# calendar-module.net
KiCad netlist of a schematic drawn in EAGLE
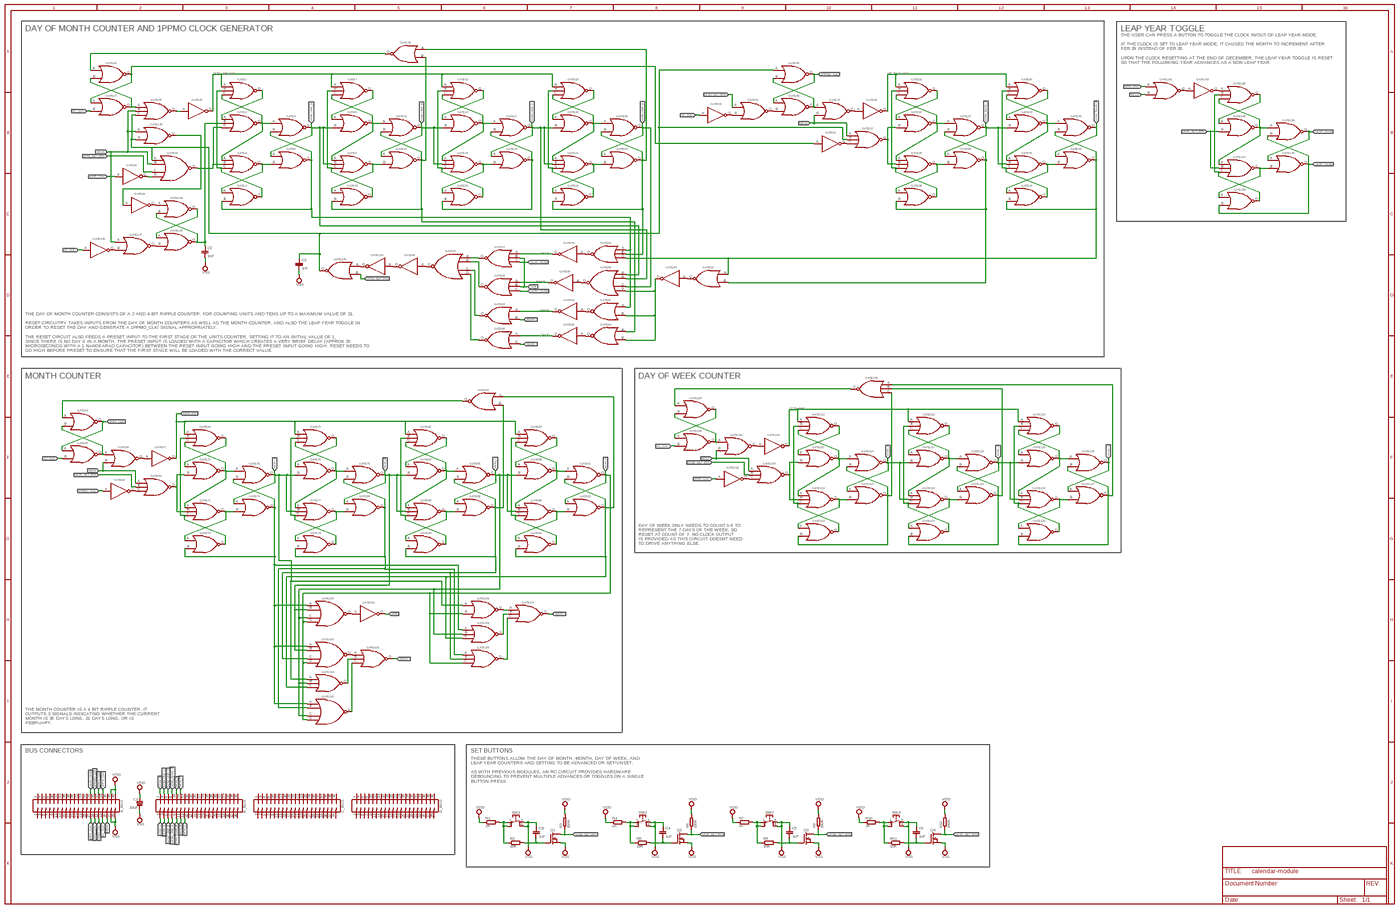
[diagram p0: schematic, sheet 1, overview]
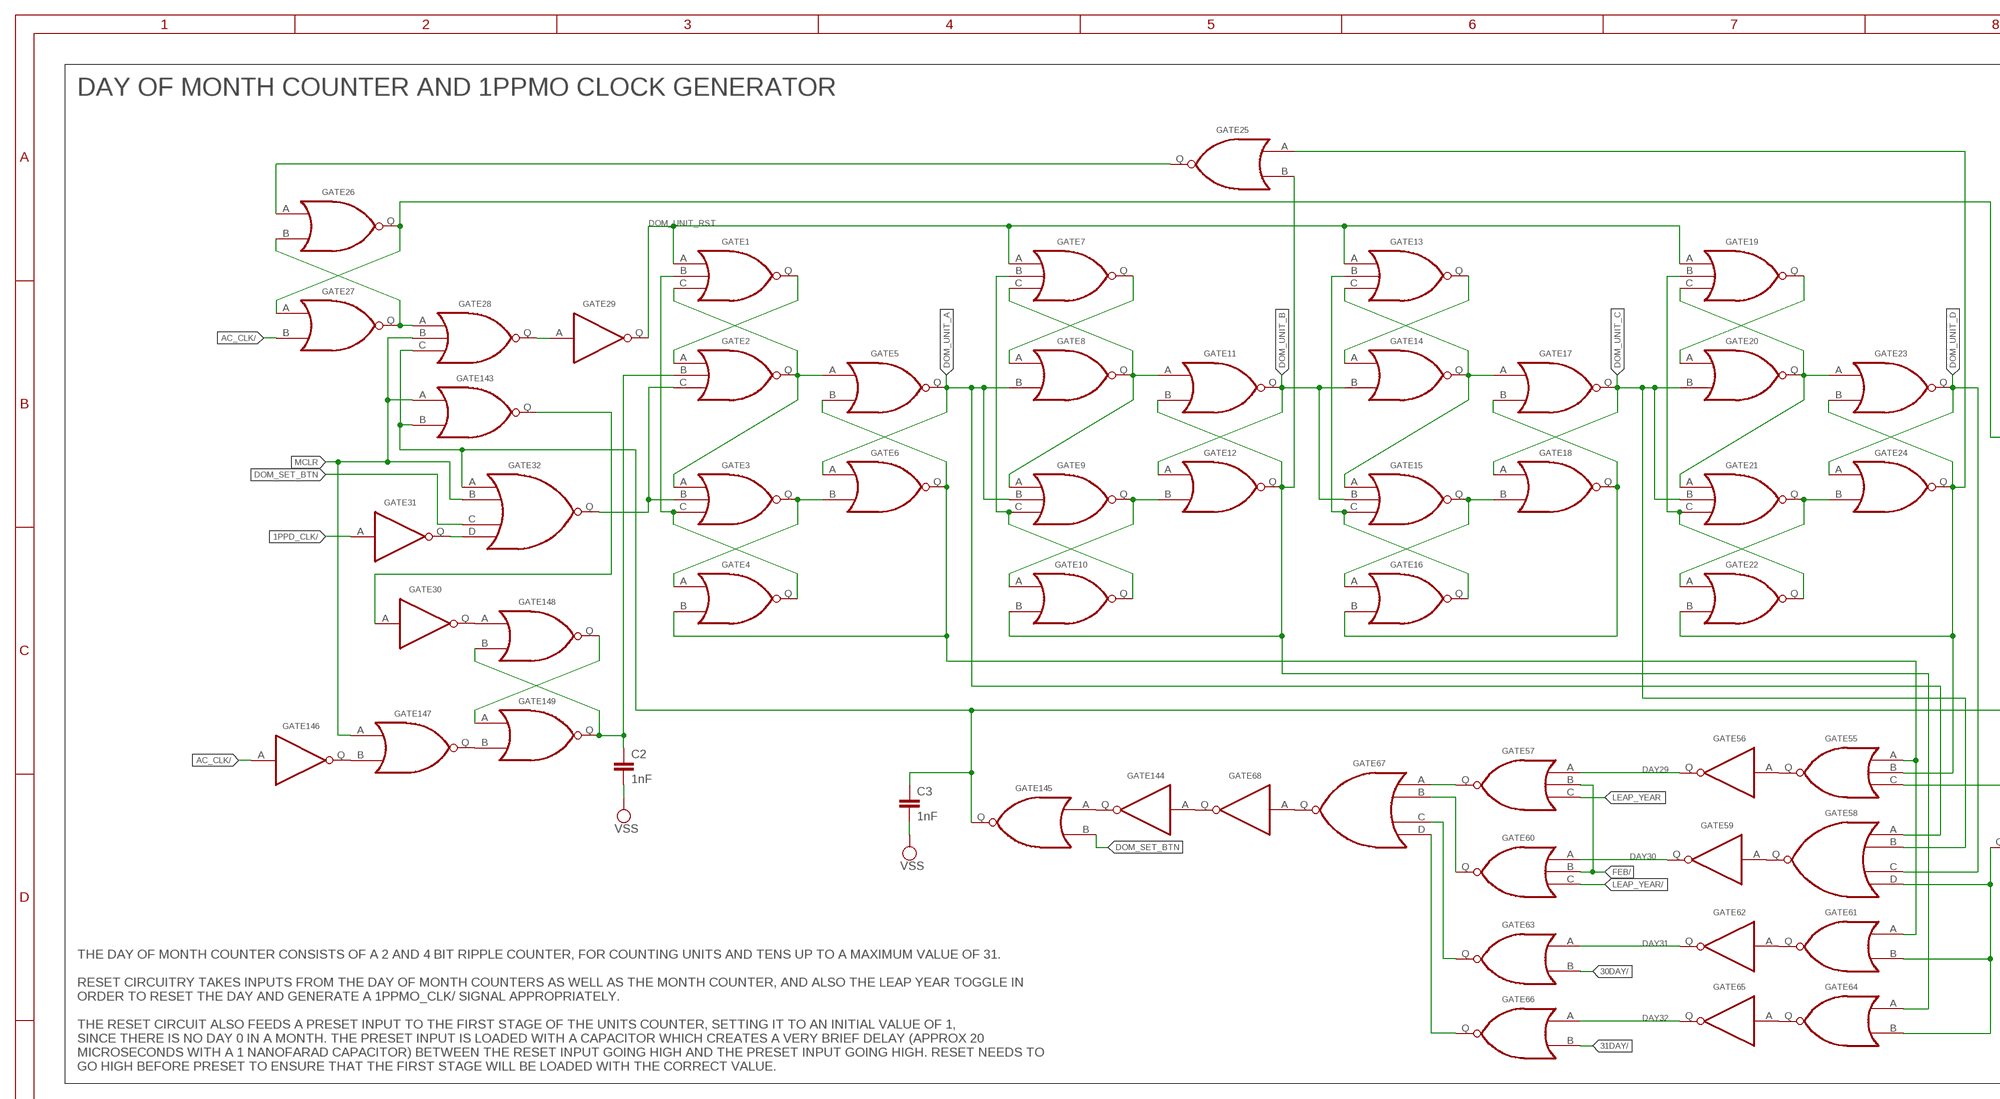
[diagram p1: schematic, sheet 1, part 1 of 4]
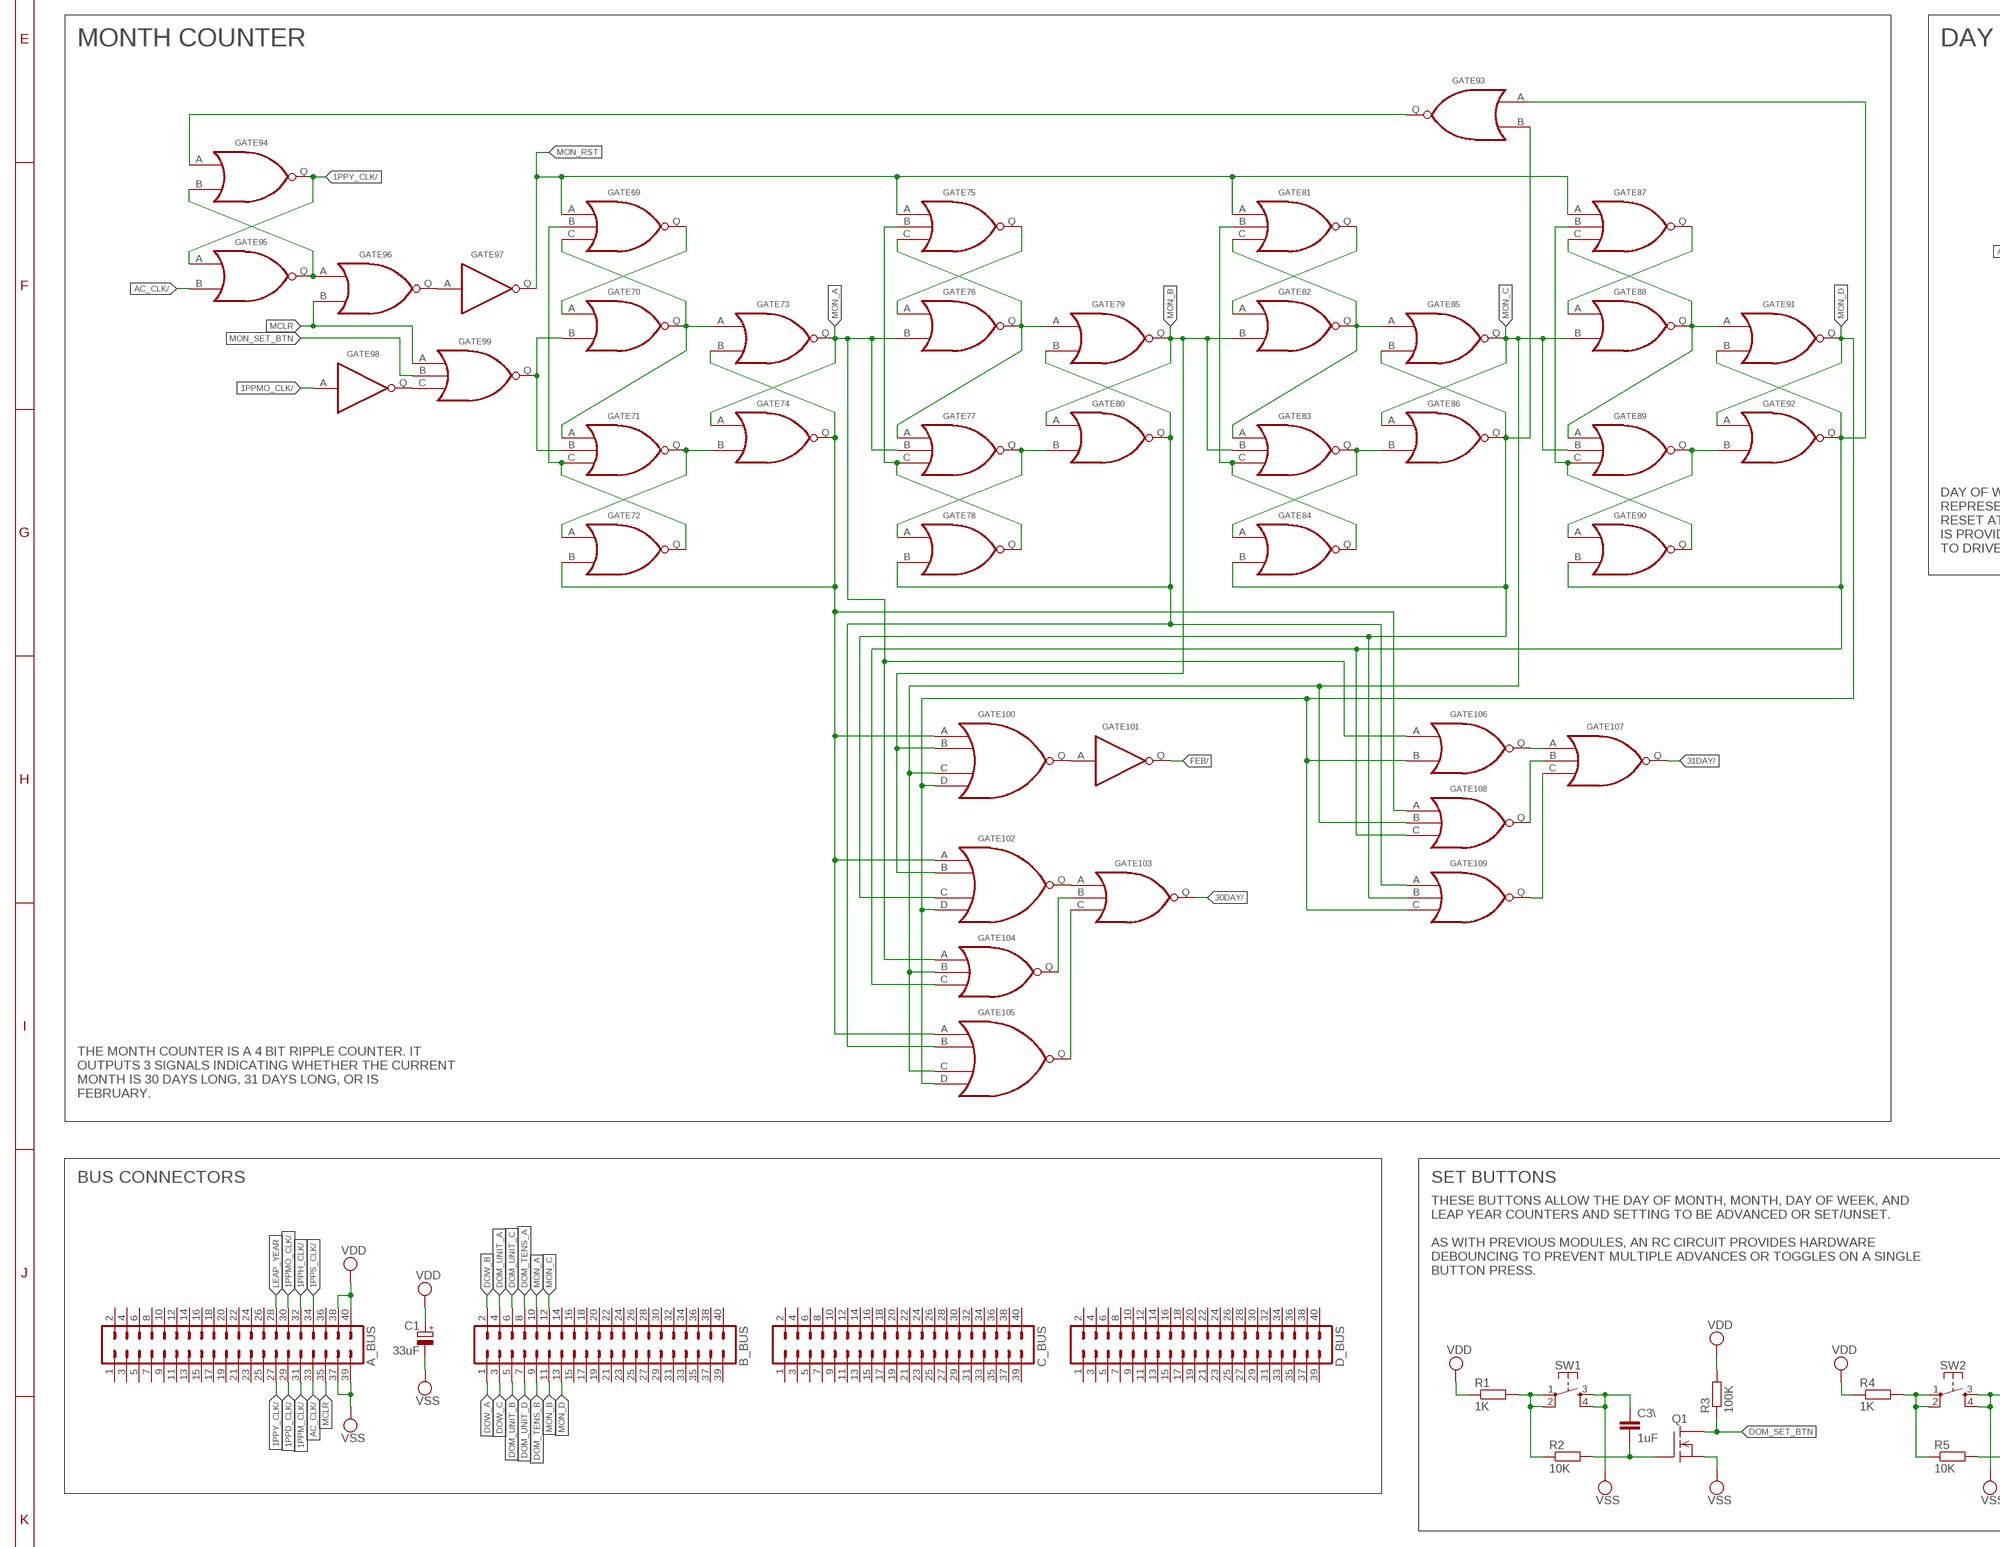
[diagram p2: schematic, sheet 1, part 2 of 4]
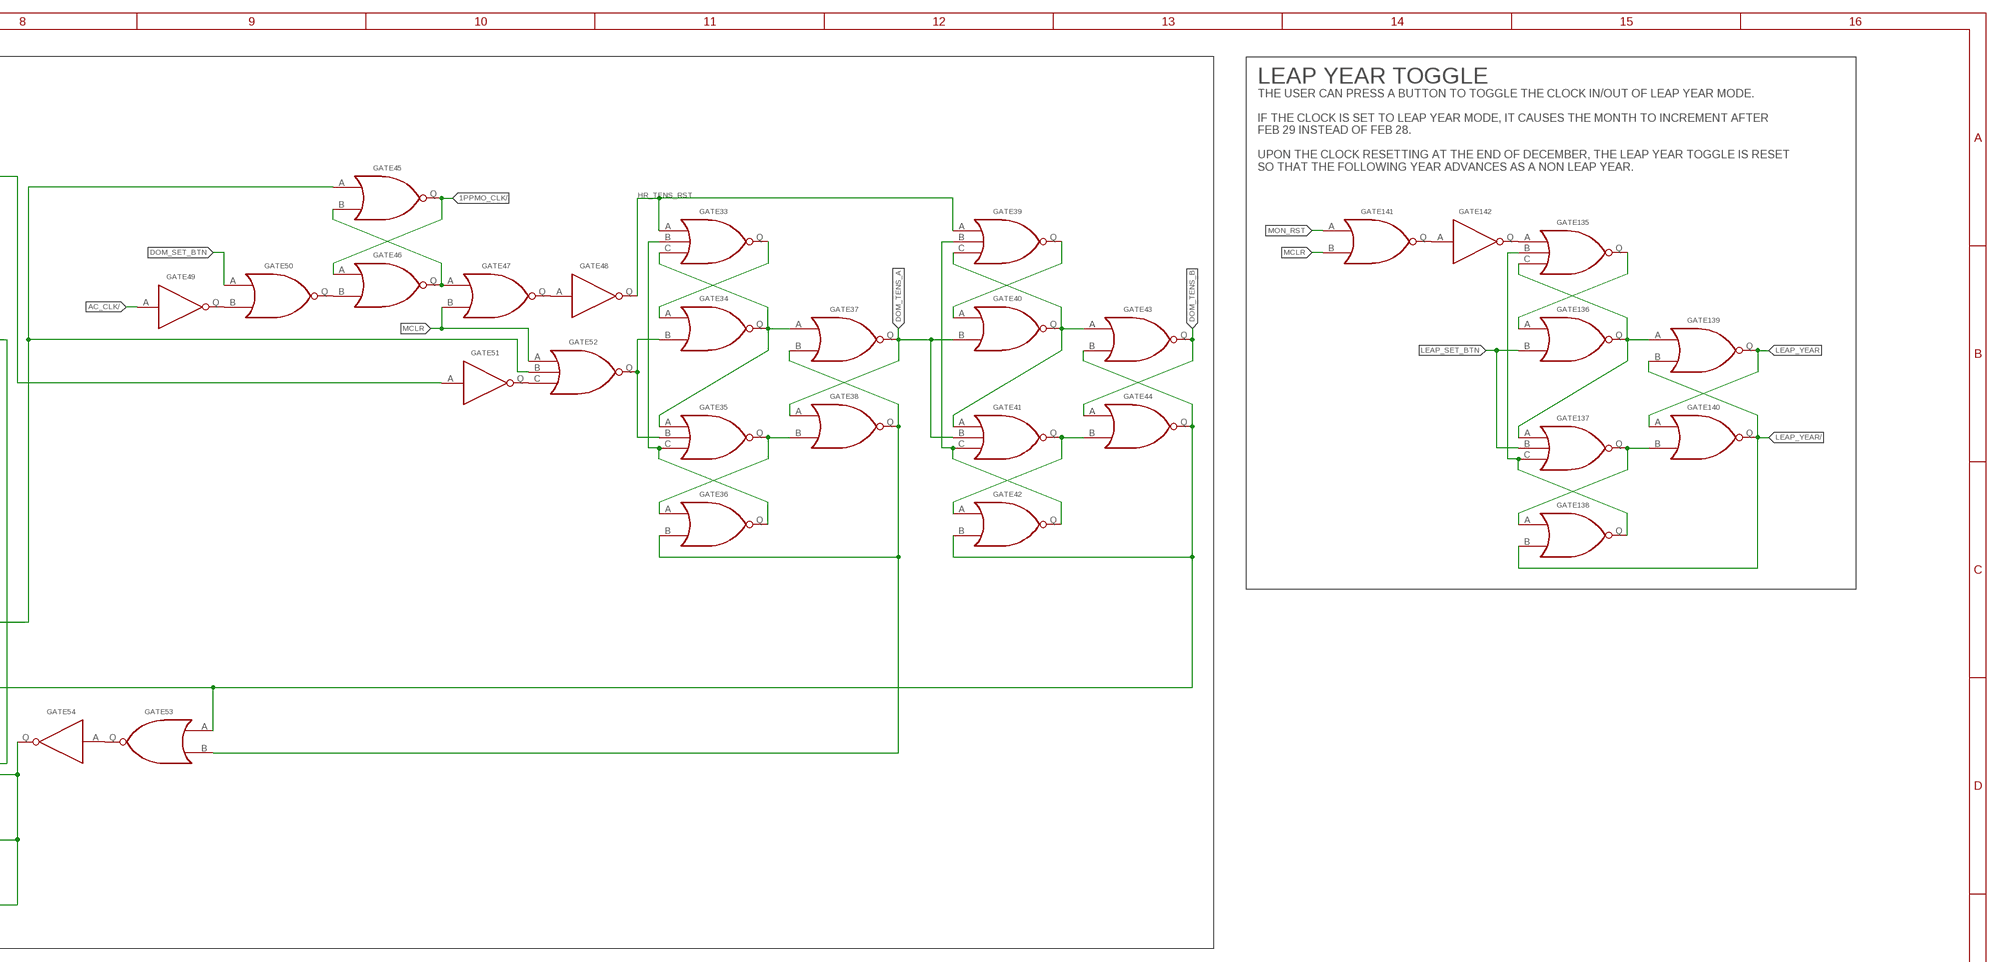
[diagram p3: schematic, sheet 1, part 3 of 4]
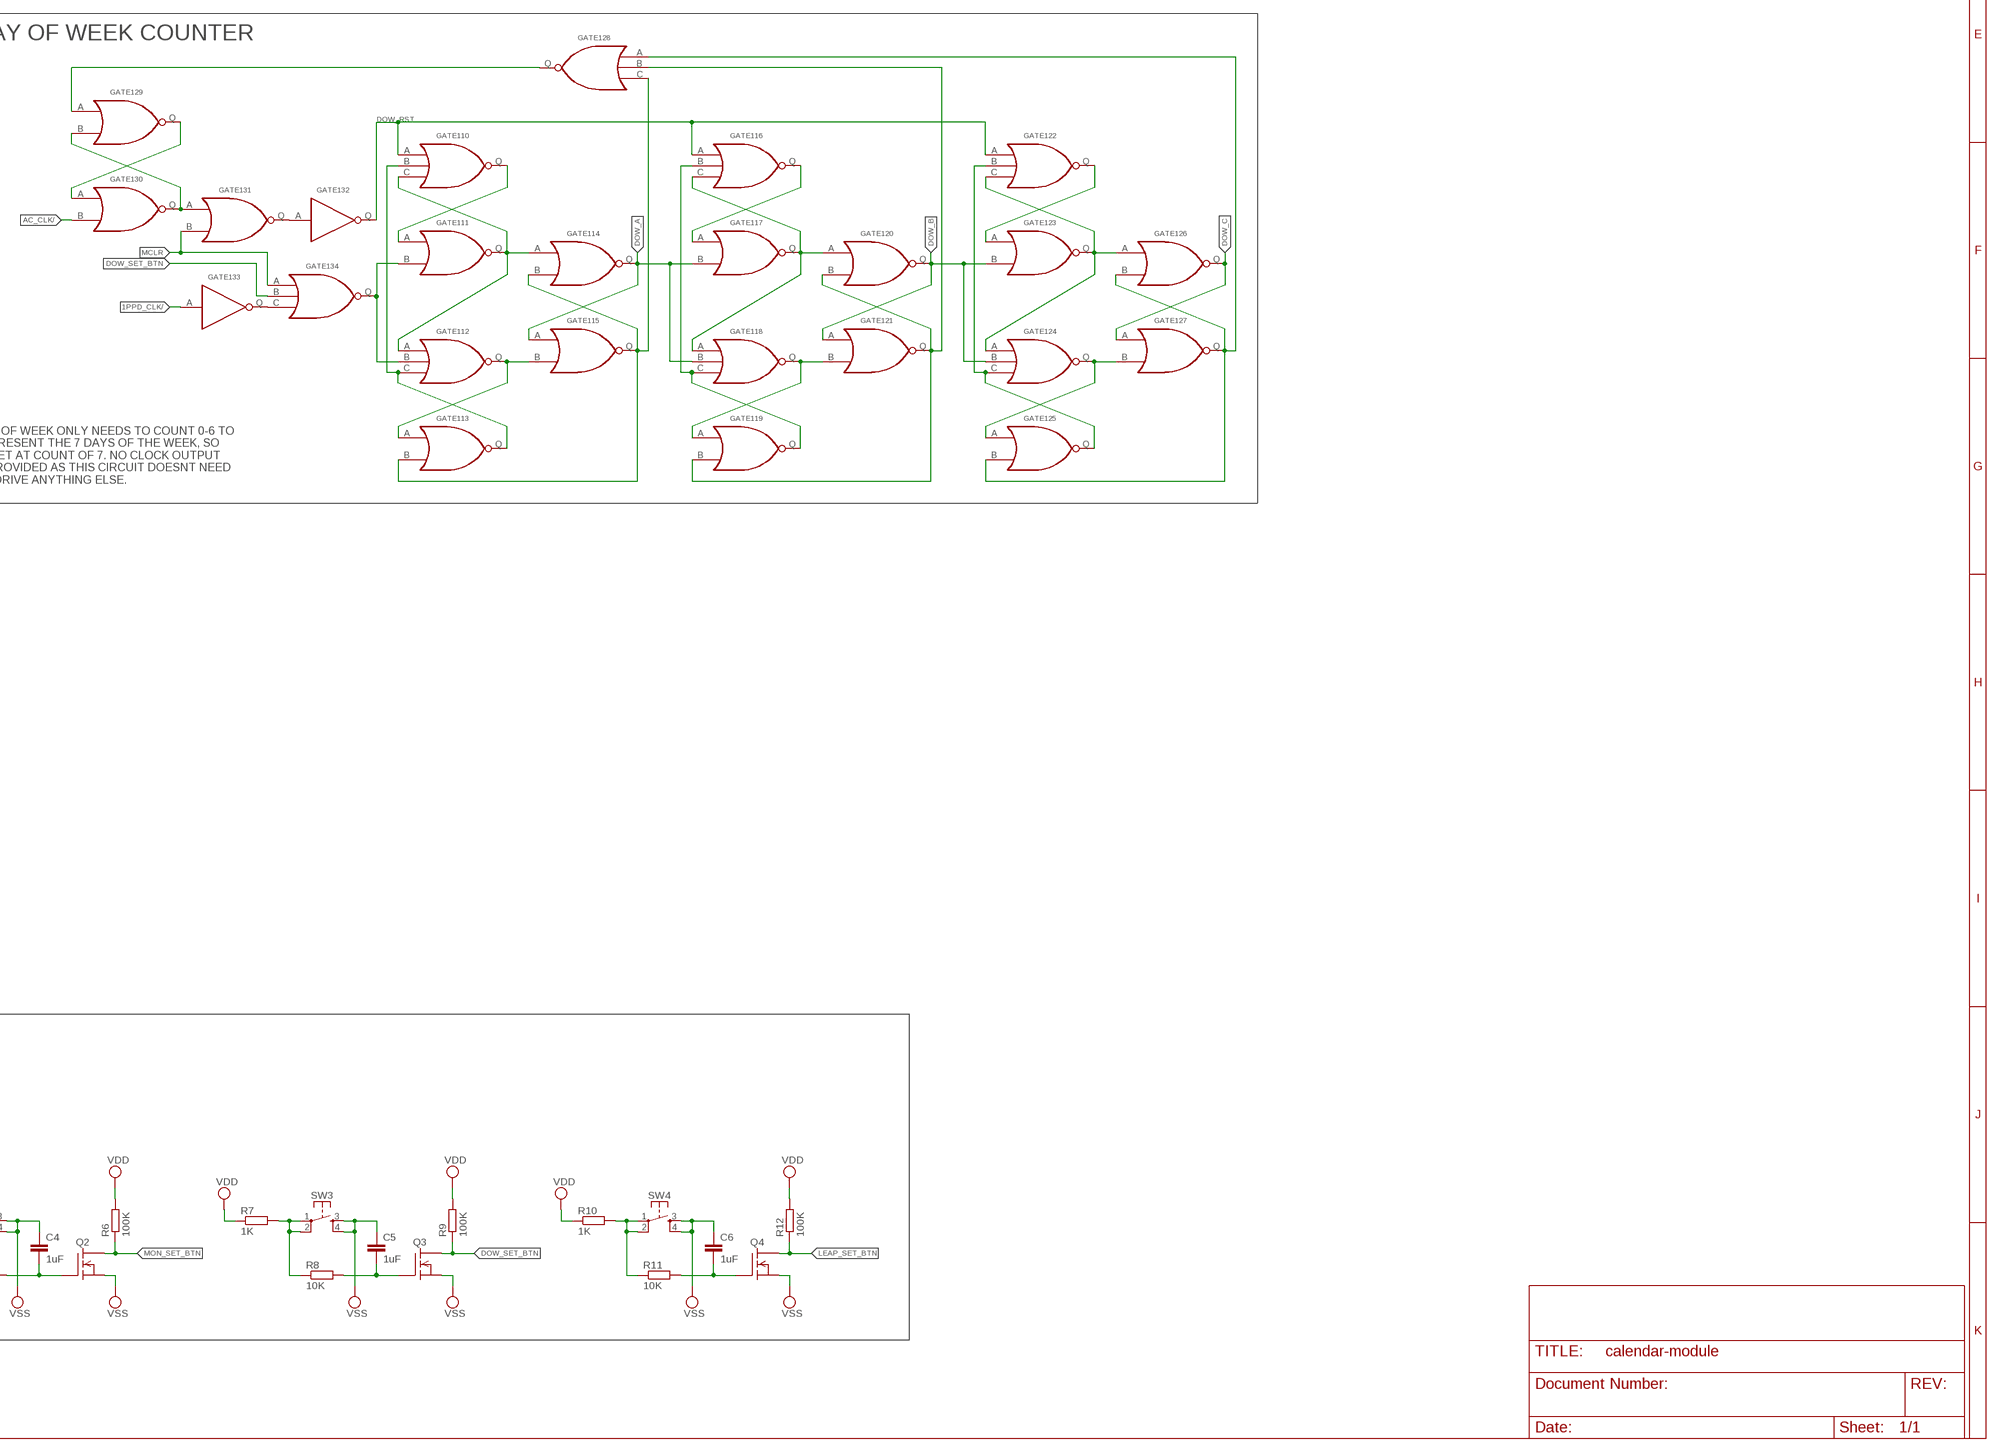
[diagram p4: schematic, sheet 1, part 4 of 4]

(export (version "E")
  (design (tool "Eeschema 10.0.6"))
  (components
    (comp (ref "A_BUS")
      (value "MA20-2")
      (footprint "eagle-import:MA20-2")
      (libsource (lib "eagle-import") (part "MA20-2"))
    )
    (comp (ref "B_BUS")
      (value "MA20-2")
      (footprint "eagle-import:MA20-2")
      (libsource (lib "eagle-import") (part "MA20-2"))
    )
    (comp (ref "C1")
      (value "33uF")
      (footprint "eagle-import:E2,5-6")
      (libsource (lib "eagle-import") (part "CPOL-EUE2.5-6"))
    )
    (comp (ref "C2")
      (value "1nF")
      (footprint "eagle-import:C050-025X075")
      (libsource (lib "eagle-import") (part "C-EU050-025X075"))
    )
    (comp (ref "C3")
      (value "1nF")
      (footprint "eagle-import:C050-025X075")
      (libsource (lib "eagle-import") (part "C-EU050-025X075"))
    )
    (comp (ref "C3\\")
      (value "1uF")
      (footprint "eagle-import:C050-025X075")
      (libsource (lib "eagle-import") (part "C-EU050-025X075"))
    )
    (comp (ref "C4")
      (value "1uF")
      (footprint "eagle-import:C050-025X075")
      (libsource (lib "eagle-import") (part "C-EU050-025X075"))
    )
    (comp (ref "C5")
      (value "1uF")
      (footprint "eagle-import:C050-025X075")
      (libsource (lib "eagle-import") (part "C-EU050-025X075"))
    )
    (comp (ref "C6")
      (value "1uF")
      (footprint "eagle-import:C050-025X075")
      (libsource (lib "eagle-import") (part "C-EU050-025X075"))
    )
    (comp (ref "C_BUS")
      (value "MA20-2")
      (footprint "eagle-import:MA20-2")
      (libsource (lib "eagle-import") (part "MA20-2"))
    )
    (comp (ref "D_BUS")
      (value "MA20-2")
      (footprint "eagle-import:MA20-2")
      (libsource (lib "eagle-import") (part "MA20-2"))
    )
    (comp (ref "GATE1")
      (value "3NOR")
      (footprint "eagle-import:3NOR")
      (libsource (lib "eagle-import") (part "3NOR"))
    )
    (comp (ref "GATE2")
      (value "3NOR")
      (footprint "eagle-import:3NOR")
      (libsource (lib "eagle-import") (part "3NOR"))
    )
    (comp (ref "GATE3")
      (value "3NOR")
      (footprint "eagle-import:3NOR")
      (libsource (lib "eagle-import") (part "3NOR"))
    )
    (comp (ref "GATE4")
      (value "2NOR")
      (footprint "eagle-import:2NOR")
      (libsource (lib "eagle-import") (part "2NOR"))
    )
    (comp (ref "GATE5")
      (value "2NOR")
      (footprint "eagle-import:2NOR")
      (libsource (lib "eagle-import") (part "2NOR"))
    )
    (comp (ref "GATE6")
      (value "2NOR")
      (footprint "eagle-import:2NOR")
      (libsource (lib "eagle-import") (part "2NOR"))
    )
    (comp (ref "GATE7")
      (value "3NOR")
      (footprint "eagle-import:3NOR")
      (libsource (lib "eagle-import") (part "3NOR"))
    )
    (comp (ref "GATE8")
      (value "2NOR")
      (footprint "eagle-import:2NOR")
      (libsource (lib "eagle-import") (part "2NOR"))
    )
    (comp (ref "GATE9")
      (value "3NOR")
      (footprint "eagle-import:3NOR")
      (libsource (lib "eagle-import") (part "3NOR"))
    )
    (comp (ref "GATE10")
      (value "2NOR")
      (footprint "eagle-import:2NOR")
      (libsource (lib "eagle-import") (part "2NOR"))
    )
    (comp (ref "GATE11")
      (value "2NOR")
      (footprint "eagle-import:2NOR")
      (libsource (lib "eagle-import") (part "2NOR"))
    )
    (comp (ref "GATE12")
      (value "2NOR")
      (footprint "eagle-import:2NOR")
      (libsource (lib "eagle-import") (part "2NOR"))
    )
    (comp (ref "GATE13")
      (value "3NOR")
      (footprint "eagle-import:3NOR")
      (libsource (lib "eagle-import") (part "3NOR"))
    )
    (comp (ref "GATE14")
      (value "2NOR")
      (footprint "eagle-import:2NOR")
      (libsource (lib "eagle-import") (part "2NOR"))
    )
    (comp (ref "GATE15")
      (value "3NOR")
      (footprint "eagle-import:3NOR")
      (libsource (lib "eagle-import") (part "3NOR"))
    )
    (comp (ref "GATE16")
      (value "2NOR")
      (footprint "eagle-import:2NOR")
      (libsource (lib "eagle-import") (part "2NOR"))
    )
    (comp (ref "GATE17")
      (value "2NOR")
      (footprint "eagle-import:2NOR")
      (libsource (lib "eagle-import") (part "2NOR"))
    )
    (comp (ref "GATE18")
      (value "2NOR")
      (footprint "eagle-import:2NOR")
      (libsource (lib "eagle-import") (part "2NOR"))
    )
    (comp (ref "GATE19")
      (value "3NOR")
      (footprint "eagle-import:3NOR")
      (libsource (lib "eagle-import") (part "3NOR"))
    )
    (comp (ref "GATE20")
      (value "2NOR")
      (footprint "eagle-import:2NOR")
      (libsource (lib "eagle-import") (part "2NOR"))
    )
    (comp (ref "GATE21")
      (value "3NOR")
      (footprint "eagle-import:3NOR")
      (libsource (lib "eagle-import") (part "3NOR"))
    )
    (comp (ref "GATE22")
      (value "2NOR")
      (footprint "eagle-import:2NOR")
      (libsource (lib "eagle-import") (part "2NOR"))
    )
    (comp (ref "GATE23")
      (value "2NOR")
      (footprint "eagle-import:2NOR")
      (libsource (lib "eagle-import") (part "2NOR"))
    )
    (comp (ref "GATE24")
      (value "2NOR")
      (footprint "eagle-import:2NOR")
      (libsource (lib "eagle-import") (part "2NOR"))
    )
    (comp (ref "GATE25")
      (value "2NOR")
      (footprint "eagle-import:2NOR")
      (libsource (lib "eagle-import") (part "2NOR"))
    )
    (comp (ref "GATE26")
      (value "2NOR")
      (footprint "eagle-import:2NOR")
      (libsource (lib "eagle-import") (part "2NOR"))
    )
    (comp (ref "GATE27")
      (value "2NOR")
      (footprint "eagle-import:2NOR")
      (libsource (lib "eagle-import") (part "2NOR"))
    )
    (comp (ref "GATE28")
      (value "3NOR")
      (footprint "eagle-import:3NOR")
      (libsource (lib "eagle-import") (part "3NOR"))
    )
    (comp (ref "GATE29")
      (value "INVERTER")
      (footprint "eagle-import:INVERTER")
      (libsource (lib "eagle-import") (part "INVERTER"))
    )
    (comp (ref "GATE30")
      (value "INVERTER")
      (footprint "eagle-import:INVERTER")
      (libsource (lib "eagle-import") (part "INVERTER"))
    )
    (comp (ref "GATE31")
      (value "INVERTER")
      (footprint "eagle-import:INVERTER")
      (libsource (lib "eagle-import") (part "INVERTER"))
    )
    (comp (ref "GATE32")
      (value "4NOR")
      (footprint "eagle-import:4NOR")
      (libsource (lib "eagle-import") (part "4NOR"))
    )
    (comp (ref "GATE33")
      (value "3NOR")
      (footprint "eagle-import:3NOR")
      (libsource (lib "eagle-import") (part "3NOR"))
    )
    (comp (ref "GATE34")
      (value "2NOR")
      (footprint "eagle-import:2NOR")
      (libsource (lib "eagle-import") (part "2NOR"))
    )
    (comp (ref "GATE35")
      (value "3NOR")
      (footprint "eagle-import:3NOR")
      (libsource (lib "eagle-import") (part "3NOR"))
    )
    (comp (ref "GATE36")
      (value "2NOR")
      (footprint "eagle-import:2NOR")
      (libsource (lib "eagle-import") (part "2NOR"))
    )
    (comp (ref "GATE37")
      (value "2NOR")
      (footprint "eagle-import:2NOR")
      (libsource (lib "eagle-import") (part "2NOR"))
    )
    (comp (ref "GATE38")
      (value "2NOR")
      (footprint "eagle-import:2NOR")
      (libsource (lib "eagle-import") (part "2NOR"))
    )
    (comp (ref "GATE39")
      (value "3NOR")
      (footprint "eagle-import:3NOR")
      (libsource (lib "eagle-import") (part "3NOR"))
    )
    (comp (ref "GATE40")
      (value "2NOR")
      (footprint "eagle-import:2NOR")
      (libsource (lib "eagle-import") (part "2NOR"))
    )
    (comp (ref "GATE41")
      (value "3NOR")
      (footprint "eagle-import:3NOR")
      (libsource (lib "eagle-import") (part "3NOR"))
    )
    (comp (ref "GATE42")
      (value "2NOR")
      (footprint "eagle-import:2NOR")
      (libsource (lib "eagle-import") (part "2NOR"))
    )
    (comp (ref "GATE43")
      (value "2NOR")
      (footprint "eagle-import:2NOR")
      (libsource (lib "eagle-import") (part "2NOR"))
    )
    (comp (ref "GATE44")
      (value "2NOR")
      (footprint "eagle-import:2NOR")
      (libsource (lib "eagle-import") (part "2NOR"))
    )
    (comp (ref "GATE45")
      (value "2NOR")
      (footprint "eagle-import:2NOR")
      (libsource (lib "eagle-import") (part "2NOR"))
    )
    (comp (ref "GATE46")
      (value "2NOR")
      (footprint "eagle-import:2NOR")
      (libsource (lib "eagle-import") (part "2NOR"))
    )
    (comp (ref "GATE47")
      (value "2NOR")
      (footprint "eagle-import:2NOR")
      (libsource (lib "eagle-import") (part "2NOR"))
    )
    (comp (ref "GATE48")
      (value "INVERTER")
      (footprint "eagle-import:INVERTER")
      (libsource (lib "eagle-import") (part "INVERTER"))
    )
    (comp (ref "GATE49")
      (value "INVERTER")
      (footprint "eagle-import:INVERTER")
      (libsource (lib "eagle-import") (part "INVERTER"))
    )
    (comp (ref "GATE50")
      (value "2NOR")
      (footprint "eagle-import:2NOR")
      (libsource (lib "eagle-import") (part "2NOR"))
    )
    (comp (ref "GATE51")
      (value "INVERTER")
      (footprint "eagle-import:INVERTER")
      (libsource (lib "eagle-import") (part "INVERTER"))
    )
    (comp (ref "GATE52")
      (value "3NOR")
      (footprint "eagle-import:3NOR")
      (libsource (lib "eagle-import") (part "3NOR"))
    )
    (comp (ref "GATE53")
      (value "2NOR")
      (footprint "eagle-import:2NOR")
      (libsource (lib "eagle-import") (part "2NOR"))
    )
    (comp (ref "GATE54")
      (value "INVERTER")
      (footprint "eagle-import:INVERTER")
      (libsource (lib "eagle-import") (part "INVERTER"))
    )
    (comp (ref "GATE55")
      (value "3NOR")
      (footprint "eagle-import:3NOR")
      (libsource (lib "eagle-import") (part "3NOR"))
    )
    (comp (ref "GATE56")
      (value "INVERTER")
      (footprint "eagle-import:INVERTER")
      (libsource (lib "eagle-import") (part "INVERTER"))
    )
    (comp (ref "GATE57")
      (value "3NOR")
      (footprint "eagle-import:3NOR")
      (libsource (lib "eagle-import") (part "3NOR"))
    )
    (comp (ref "GATE58")
      (value "4NOR")
      (footprint "eagle-import:4NOR")
      (libsource (lib "eagle-import") (part "4NOR"))
    )
    (comp (ref "GATE59")
      (value "INVERTER")
      (footprint "eagle-import:INVERTER")
      (libsource (lib "eagle-import") (part "INVERTER"))
    )
    (comp (ref "GATE60")
      (value "3NOR")
      (footprint "eagle-import:3NOR")
      (libsource (lib "eagle-import") (part "3NOR"))
    )
    (comp (ref "GATE61")
      (value "2NOR")
      (footprint "eagle-import:2NOR")
      (libsource (lib "eagle-import") (part "2NOR"))
    )
    (comp (ref "GATE62")
      (value "INVERTER")
      (footprint "eagle-import:INVERTER")
      (libsource (lib "eagle-import") (part "INVERTER"))
    )
    (comp (ref "GATE63")
      (value "2NOR")
      (footprint "eagle-import:2NOR")
      (libsource (lib "eagle-import") (part "2NOR"))
    )
    (comp (ref "GATE64")
      (value "2NOR")
      (footprint "eagle-import:2NOR")
      (libsource (lib "eagle-import") (part "2NOR"))
    )
    (comp (ref "GATE65")
      (value "INVERTER")
      (footprint "eagle-import:INVERTER")
      (libsource (lib "eagle-import") (part "INVERTER"))
    )
    (comp (ref "GATE66")
      (value "2NOR")
      (footprint "eagle-import:2NOR")
      (libsource (lib "eagle-import") (part "2NOR"))
    )
    (comp (ref "GATE67")
      (value "4NOR")
      (footprint "eagle-import:4NOR")
      (libsource (lib "eagle-import") (part "4NOR"))
    )
    (comp (ref "GATE68")
      (value "INVERTER")
      (footprint "eagle-import:INVERTER")
      (libsource (lib "eagle-import") (part "INVERTER"))
    )
    (comp (ref "GATE69")
      (value "3NOR")
      (footprint "eagle-import:3NOR")
      (libsource (lib "eagle-import") (part "3NOR"))
    )
    (comp (ref "GATE70")
      (value "2NOR")
      (footprint "eagle-import:2NOR")
      (libsource (lib "eagle-import") (part "2NOR"))
    )
    (comp (ref "GATE71")
      (value "3NOR")
      (footprint "eagle-import:3NOR")
      (libsource (lib "eagle-import") (part "3NOR"))
    )
    (comp (ref "GATE72")
      (value "2NOR")
      (footprint "eagle-import:2NOR")
      (libsource (lib "eagle-import") (part "2NOR"))
    )
    (comp (ref "GATE73")
      (value "2NOR")
      (footprint "eagle-import:2NOR")
      (libsource (lib "eagle-import") (part "2NOR"))
    )
    (comp (ref "GATE74")
      (value "2NOR")
      (footprint "eagle-import:2NOR")
      (libsource (lib "eagle-import") (part "2NOR"))
    )
    (comp (ref "GATE75")
      (value "3NOR")
      (footprint "eagle-import:3NOR")
      (libsource (lib "eagle-import") (part "3NOR"))
    )
    (comp (ref "GATE76")
      (value "2NOR")
      (footprint "eagle-import:2NOR")
      (libsource (lib "eagle-import") (part "2NOR"))
    )
    (comp (ref "GATE77")
      (value "3NOR")
      (footprint "eagle-import:3NOR")
      (libsource (lib "eagle-import") (part "3NOR"))
    )
    (comp (ref "GATE78")
      (value "2NOR")
      (footprint "eagle-import:2NOR")
      (libsource (lib "eagle-import") (part "2NOR"))
    )
    (comp (ref "GATE79")
      (value "2NOR")
      (footprint "eagle-import:2NOR")
      (libsource (lib "eagle-import") (part "2NOR"))
    )
    (comp (ref "GATE80")
      (value "2NOR")
      (footprint "eagle-import:2NOR")
      (libsource (lib "eagle-import") (part "2NOR"))
    )
    (comp (ref "GATE81")
      (value "3NOR")
      (footprint "eagle-import:3NOR")
      (libsource (lib "eagle-import") (part "3NOR"))
    )
    (comp (ref "GATE82")
      (value "2NOR")
      (footprint "eagle-import:2NOR")
      (libsource (lib "eagle-import") (part "2NOR"))
    )
    (comp (ref "GATE83")
      (value "3NOR")
      (footprint "eagle-import:3NOR")
      (libsource (lib "eagle-import") (part "3NOR"))
    )
    (comp (ref "GATE84")
      (value "2NOR")
      (footprint "eagle-import:2NOR")
      (libsource (lib "eagle-import") (part "2NOR"))
    )
    (comp (ref "GATE85")
      (value "2NOR")
      (footprint "eagle-import:2NOR")
      (libsource (lib "eagle-import") (part "2NOR"))
    )
    (comp (ref "GATE86")
      (value "2NOR")
      (footprint "eagle-import:2NOR")
      (libsource (lib "eagle-import") (part "2NOR"))
    )
    (comp (ref "GATE87")
      (value "3NOR")
      (footprint "eagle-import:3NOR")
      (libsource (lib "eagle-import") (part "3NOR"))
    )
    (comp (ref "GATE88")
      (value "2NOR")
      (footprint "eagle-import:2NOR")
      (libsource (lib "eagle-import") (part "2NOR"))
    )
    (comp (ref "GATE89")
      (value "3NOR")
      (footprint "eagle-import:3NOR")
      (libsource (lib "eagle-import") (part "3NOR"))
    )
    (comp (ref "GATE90")
      (value "2NOR")
      (footprint "eagle-import:2NOR")
      (libsource (lib "eagle-import") (part "2NOR"))
    )
    (comp (ref "GATE91")
      (value "2NOR")
      (footprint "eagle-import:2NOR")
      (libsource (lib "eagle-import") (part "2NOR"))
    )
    (comp (ref "GATE92")
      (value "2NOR")
      (footprint "eagle-import:2NOR")
      (libsource (lib "eagle-import") (part "2NOR"))
    )
    (comp (ref "GATE93")
      (value "2NOR")
      (footprint "eagle-import:2NOR")
      (libsource (lib "eagle-import") (part "2NOR"))
    )
    (comp (ref "GATE94")
      (value "2NOR")
      (footprint "eagle-import:2NOR")
      (libsource (lib "eagle-import") (part "2NOR"))
    )
    (comp (ref "GATE95")
      (value "2NOR")
      (footprint "eagle-import:2NOR")
      (libsource (lib "eagle-import") (part "2NOR"))
    )
    (comp (ref "GATE96")
      (value "2NOR")
      (footprint "eagle-import:2NOR")
      (libsource (lib "eagle-import") (part "2NOR"))
    )
    (comp (ref "GATE97")
      (value "INVERTER")
      (footprint "eagle-import:INVERTER")
      (libsource (lib "eagle-import") (part "INVERTER"))
    )
    (comp (ref "GATE98")
      (value "INVERTER")
      (footprint "eagle-import:INVERTER")
      (libsource (lib "eagle-import") (part "INVERTER"))
    )
    (comp (ref "GATE99")
      (value "3NOR")
      (footprint "eagle-import:3NOR")
      (libsource (lib "eagle-import") (part "3NOR"))
    )
    (comp (ref "GATE100")
      (value "4NOR")
      (footprint "eagle-import:4NOR")
      (libsource (lib "eagle-import") (part "4NOR"))
    )
    (comp (ref "GATE101")
      (value "INVERTER")
      (footprint "eagle-import:INVERTER")
      (libsource (lib "eagle-import") (part "INVERTER"))
    )
    (comp (ref "GATE102")
      (value "4NOR")
      (footprint "eagle-import:4NOR")
      (libsource (lib "eagle-import") (part "4NOR"))
    )
    (comp (ref "GATE103")
      (value "3NOR")
      (footprint "eagle-import:3NOR")
      (libsource (lib "eagle-import") (part "3NOR"))
    )
    (comp (ref "GATE104")
      (value "3NOR")
      (footprint "eagle-import:3NOR")
      (libsource (lib "eagle-import") (part "3NOR"))
    )
    (comp (ref "GATE105")
      (value "4NOR")
      (footprint "eagle-import:4NOR")
      (libsource (lib "eagle-import") (part "4NOR"))
    )
    (comp (ref "GATE106")
      (value "2NOR")
      (footprint "eagle-import:2NOR")
      (libsource (lib "eagle-import") (part "2NOR"))
    )
    (comp (ref "GATE107")
      (value "3NOR")
      (footprint "eagle-import:3NOR")
      (libsource (lib "eagle-import") (part "3NOR"))
    )
    (comp (ref "GATE108")
      (value "3NOR")
      (footprint "eagle-import:3NOR")
      (libsource (lib "eagle-import") (part "3NOR"))
    )
    (comp (ref "GATE109")
      (value "3NOR")
      (footprint "eagle-import:3NOR")
      (libsource (lib "eagle-import") (part "3NOR"))
    )
    (comp (ref "GATE110")
      (value "3NOR")
      (footprint "eagle-import:3NOR")
      (libsource (lib "eagle-import") (part "3NOR"))
    )
    (comp (ref "GATE111")
      (value "2NOR")
      (footprint "eagle-import:2NOR")
      (libsource (lib "eagle-import") (part "2NOR"))
    )
    (comp (ref "GATE112")
      (value "3NOR")
      (footprint "eagle-import:3NOR")
      (libsource (lib "eagle-import") (part "3NOR"))
    )
    (comp (ref "GATE113")
      (value "2NOR")
      (footprint "eagle-import:2NOR")
      (libsource (lib "eagle-import") (part "2NOR"))
    )
    (comp (ref "GATE114")
      (value "2NOR")
      (footprint "eagle-import:2NOR")
      (libsource (lib "eagle-import") (part "2NOR"))
    )
    (comp (ref "GATE115")
      (value "2NOR")
      (footprint "eagle-import:2NOR")
      (libsource (lib "eagle-import") (part "2NOR"))
    )
    (comp (ref "GATE116")
      (value "3NOR")
      (footprint "eagle-import:3NOR")
      (libsource (lib "eagle-import") (part "3NOR"))
    )
    (comp (ref "GATE117")
      (value "2NOR")
      (footprint "eagle-import:2NOR")
      (libsource (lib "eagle-import") (part "2NOR"))
    )
    (comp (ref "GATE118")
      (value "3NOR")
      (footprint "eagle-import:3NOR")
      (libsource (lib "eagle-import") (part "3NOR"))
    )
    (comp (ref "GATE119")
      (value "2NOR")
      (footprint "eagle-import:2NOR")
      (libsource (lib "eagle-import") (part "2NOR"))
    )
    (comp (ref "GATE120")
      (value "2NOR")
      (footprint "eagle-import:2NOR")
      (libsource (lib "eagle-import") (part "2NOR"))
    )
    (comp (ref "GATE121")
      (value "2NOR")
      (footprint "eagle-import:2NOR")
      (libsource (lib "eagle-import") (part "2NOR"))
    )
    (comp (ref "GATE122")
      (value "3NOR")
      (footprint "eagle-import:3NOR")
      (libsource (lib "eagle-import") (part "3NOR"))
    )
    (comp (ref "GATE123")
      (value "2NOR")
      (footprint "eagle-import:2NOR")
      (libsource (lib "eagle-import") (part "2NOR"))
    )
    (comp (ref "GATE124")
      (value "3NOR")
      (footprint "eagle-import:3NOR")
      (libsource (lib "eagle-import") (part "3NOR"))
    )
    (comp (ref "GATE125")
      (value "2NOR")
      (footprint "eagle-import:2NOR")
      (libsource (lib "eagle-import") (part "2NOR"))
    )
    (comp (ref "GATE126")
      (value "2NOR")
      (footprint "eagle-import:2NOR")
      (libsource (lib "eagle-import") (part "2NOR"))
    )
    (comp (ref "GATE127")
      (value "2NOR")
      (footprint "eagle-import:2NOR")
      (libsource (lib "eagle-import") (part "2NOR"))
    )
    (comp (ref "GATE128")
      (value "3NOR")
      (footprint "eagle-import:3NOR")
      (libsource (lib "eagle-import") (part "3NOR"))
    )
    (comp (ref "GATE129")
      (value "2NOR")
      (footprint "eagle-import:2NOR")
      (libsource (lib "eagle-import") (part "2NOR"))
    )
    (comp (ref "GATE130")
      (value "2NOR")
      (footprint "eagle-import:2NOR")
      (libsource (lib "eagle-import") (part "2NOR"))
    )
    (comp (ref "GATE131")
      (value "2NOR")
      (footprint "eagle-import:2NOR")
      (libsource (lib "eagle-import") (part "2NOR"))
    )
    (comp (ref "GATE132")
      (value "INVERTER")
      (footprint "eagle-import:INVERTER")
      (libsource (lib "eagle-import") (part "INVERTER"))
    )
    (comp (ref "GATE133")
      (value "INVERTER")
      (footprint "eagle-import:INVERTER")
      (libsource (lib "eagle-import") (part "INVERTER"))
    )
    (comp (ref "GATE134")
      (value "3NOR")
      (footprint "eagle-import:3NOR")
      (libsource (lib "eagle-import") (part "3NOR"))
    )
    (comp (ref "GATE135")
      (value "3NOR")
      (footprint "eagle-import:3NOR")
      (libsource (lib "eagle-import") (part "3NOR"))
    )
    (comp (ref "GATE136")
      (value "2NOR")
      (footprint "eagle-import:2NOR")
      (libsource (lib "eagle-import") (part "2NOR"))
    )
    (comp (ref "GATE137")
      (value "3NOR")
      (footprint "eagle-import:3NOR")
      (libsource (lib "eagle-import") (part "3NOR"))
    )
    (comp (ref "GATE138")
      (value "2NOR")
      (footprint "eagle-import:2NOR")
      (libsource (lib "eagle-import") (part "2NOR"))
    )
    (comp (ref "GATE139")
      (value "2NOR")
      (footprint "eagle-import:2NOR")
      (libsource (lib "eagle-import") (part "2NOR"))
    )
    (comp (ref "GATE140")
      (value "2NOR")
      (footprint "eagle-import:2NOR")
      (libsource (lib "eagle-import") (part "2NOR"))
    )
    (comp (ref "GATE141")
      (value "2NOR")
      (footprint "eagle-import:2NOR")
      (libsource (lib "eagle-import") (part "2NOR"))
    )
    (comp (ref "GATE142")
      (value "INVERTER")
      (footprint "eagle-import:INVERTER")
      (libsource (lib "eagle-import") (part "INVERTER"))
    )
    (comp (ref "GATE143")
      (value "2NOR")
      (footprint "eagle-import:2NOR")
      (libsource (lib "eagle-import") (part "2NOR"))
    )
    (comp (ref "GATE144")
      (value "INVERTER")
      (footprint "eagle-import:INVERTER")
      (libsource (lib "eagle-import") (part "INVERTER"))
    )
    (comp (ref "GATE145")
      (value "2NOR")
      (footprint "eagle-import:2NOR")
      (libsource (lib "eagle-import") (part "2NOR"))
    )
    (comp (ref "GATE146")
      (value "INVERTER")
      (footprint "eagle-import:INVERTER")
      (libsource (lib "eagle-import") (part "INVERTER"))
    )
    (comp (ref "GATE147")
      (value "2NOR")
      (footprint "eagle-import:2NOR")
      (libsource (lib "eagle-import") (part "2NOR"))
    )
    (comp (ref "GATE148")
      (value "2NOR")
      (footprint "eagle-import:2NOR")
      (libsource (lib "eagle-import") (part "2NOR"))
    )
    (comp (ref "GATE149")
      (value "2NOR")
      (footprint "eagle-import:2NOR")
      (libsource (lib "eagle-import") (part "2NOR"))
    )
    (comp (ref "Q1")
      (value "2N7000")
      (footprint "eagle-import:TO-92")
      (libsource (lib "eagle-import") (part "2N7000"))
    )
    (comp (ref "Q2")
      (value "2N7000")
      (footprint "eagle-import:TO-92")
      (libsource (lib "eagle-import") (part "2N7000"))
    )
    (comp (ref "Q3")
      (value "2N7000")
      (footprint "eagle-import:TO-92")
      (libsource (lib "eagle-import") (part "2N7000"))
    )
    (comp (ref "Q4")
      (value "2N7000")
      (footprint "eagle-import:TO-92")
      (libsource (lib "eagle-import") (part "2N7000"))
    )
    (comp (ref "R1")
      (value "1K")
      (footprint "eagle-import:0207_2V")
      (libsource (lib "eagle-import") (part "R-EU_0207/2V"))
    )
    (comp (ref "R2")
      (value "10K")
      (footprint "eagle-import:0207_2V")
      (libsource (lib "eagle-import") (part "R-EU_0207/2V"))
    )
    (comp (ref "R3")
      (value "100K")
      (footprint "eagle-import:0207_2V")
      (libsource (lib "eagle-import") (part "R-EU_0207/2V"))
    )
    (comp (ref "R4")
      (value "1K")
      (footprint "eagle-import:0207_2V")
      (libsource (lib "eagle-import") (part "R-EU_0207/2V"))
    )
    (comp (ref "R5")
      (value "10K")
      (footprint "eagle-import:0207_2V")
      (libsource (lib "eagle-import") (part "R-EU_0207/2V"))
    )
    (comp (ref "R6")
      (value "100K")
      (footprint "eagle-import:0207_2V")
      (libsource (lib "eagle-import") (part "R-EU_0207/2V"))
    )
    (comp (ref "R7")
      (value "1K")
      (footprint "eagle-import:0207_2V")
      (libsource (lib "eagle-import") (part "R-EU_0207/2V"))
    )
    (comp (ref "R8")
      (value "10K")
      (footprint "eagle-import:0207_2V")
      (libsource (lib "eagle-import") (part "R-EU_0207/2V"))
    )
    (comp (ref "R9")
      (value "100K")
      (footprint "eagle-import:0207_2V")
      (libsource (lib "eagle-import") (part "R-EU_0207/2V"))
    )
    (comp (ref "R10")
      (value "1K")
      (footprint "eagle-import:0207_2V")
      (libsource (lib "eagle-import") (part "R-EU_0207/2V"))
    )
    (comp (ref "R11")
      (value "10K")
      (footprint "eagle-import:0207_2V")
      (libsource (lib "eagle-import") (part "R-EU_0207/2V"))
    )
    (comp (ref "R12")
      (value "100K")
      (footprint "eagle-import:0207_2V")
      (libsource (lib "eagle-import") (part "R-EU_0207/2V"))
    )
    (comp (ref "SW1")
      (value "SPST-TACSWITCH")
      (footprint "eagle-import:TE-SMD-TACSWITCH")
      (libsource (lib "eagle-import") (part "SPST-TACSWITCH"))
    )
    (comp (ref "SW2")
      (value "SPST-TACSWITCH")
      (footprint "eagle-import:TE-SMD-TACSWITCH")
      (libsource (lib "eagle-import") (part "SPST-TACSWITCH"))
    )
    (comp (ref "SW3")
      (value "SPST-TACSWITCH")
      (footprint "eagle-import:TE-SMD-TACSWITCH")
      (libsource (lib "eagle-import") (part "SPST-TACSWITCH"))
    )
    (comp (ref "SW4")
      (value "SPST-TACSWITCH")
      (footprint "eagle-import:TE-SMD-TACSWITCH")
      (libsource (lib "eagle-import") (part "SPST-TACSWITCH"))
    )
  )
  (nets
    (net (code "1") (name "/DAY29") (class "Default")
      (node (ref "GATE56") (pin "Q") (pinfunction "Q_Q") (pintype "output"))
      (node (ref "GATE57") (pin "A") (pinfunction "A_A") (pintype "input"))
    )
    (net (code "2") (name "/DAY30") (class "Default")
      (node (ref "GATE59") (pin "Q") (pinfunction "Q_Q") (pintype "output"))
      (node (ref "GATE60") (pin "A") (pinfunction "A_A") (pintype "input"))
    )
    (net (code "3") (name "/DAY31") (class "Default")
      (node (ref "GATE62") (pin "Q") (pinfunction "Q_Q") (pintype "output"))
      (node (ref "GATE63") (pin "A") (pinfunction "A_A") (pintype "input"))
    )
    (net (code "4") (name "/DAY32") (class "Default")
      (node (ref "GATE65") (pin "Q") (pinfunction "Q_Q") (pintype "output"))
      (node (ref "GATE66") (pin "A") (pinfunction "A_A") (pintype "input"))
    )
    (net (code "5") (name "/DOM_UNIT_RST") (class "Default")
      (node (ref "GATE1") (pin "A") (pinfunction "A_A") (pintype "input"))
      (node (ref "GATE13") (pin "A") (pinfunction "A_A") (pintype "input"))
      (node (ref "GATE19") (pin "A") (pinfunction "A_A") (pintype "input"))
      (node (ref "GATE29") (pin "Q") (pinfunction "Q_Q") (pintype "output"))
      (node (ref "GATE7") (pin "A") (pinfunction "A_A") (pintype "input"))
    )
    (net (code "6") (name "/DOW_RST") (class "Default")
      (node (ref "GATE110") (pin "A") (pinfunction "A_A") (pintype "input"))
      (node (ref "GATE116") (pin "A") (pinfunction "A_A") (pintype "input"))
      (node (ref "GATE122") (pin "A") (pinfunction "A_A") (pintype "input"))
      (node (ref "GATE132") (pin "Q") (pinfunction "Q_Q") (pintype "output"))
    )
    (net (code "7") (name "/HR_TENS_RST") (class "Default")
      (node (ref "GATE33") (pin "A") (pinfunction "A_A") (pintype "input"))
      (node (ref "GATE39") (pin "A") (pinfunction "A_A") (pintype "input"))
      (node (ref "GATE48") (pin "Q") (pinfunction "Q_Q") (pintype "output"))
    )
    (net (code "8") (name "1PPD_CLK{slash}") (class "Default")
      (node (ref "A_BUS") (pin "29") (pinfunction "29_29") (pintype "passive"))
      (node (ref "GATE133") (pin "A") (pinfunction "A_A") (pintype "input"))
      (node (ref "GATE31") (pin "A") (pinfunction "A_A") (pintype "input"))
    )
    (net (code "9") (name "1PPH_CLK{slash}") (class "Default")
      (node (ref "A_BUS") (pin "32") (pinfunction "32_32") (pintype "passive"))
    )
    (net (code "10") (name "1PPMO_CLK{slash}") (class "Default")
      (node (ref "A_BUS") (pin "30") (pinfunction "30_30") (pintype "passive"))
      (node (ref "GATE45") (pin "Q") (pinfunction "Q_Q") (pintype "output"))
      (node (ref "GATE46") (pin "A") (pinfunction "A_A") (pintype "input"))
      (node (ref "GATE98") (pin "A") (pinfunction "A_A") (pintype "input"))
    )
    (net (code "11") (name "1PPM_CLK{slash}") (class "Default")
      (node (ref "A_BUS") (pin "31") (pinfunction "31_31") (pintype "passive"))
    )
    (net (code "12") (name "1PPS_CLK{slash}") (class "Default")
      (node (ref "A_BUS") (pin "34") (pinfunction "34_34") (pintype "passive"))
    )
    (net (code "13") (name "1PPY_CLK{slash}") (class "Default")
      (node (ref "A_BUS") (pin "27") (pinfunction "27_27") (pintype "passive"))
      (node (ref "GATE94") (pin "Q") (pinfunction "Q_Q") (pintype "output"))
      (node (ref "GATE95") (pin "A") (pinfunction "A_A") (pintype "input"))
    )
    (net (code "14") (name "30DAY{slash}") (class "Default")
      (node (ref "GATE103") (pin "Q") (pinfunction "Q_Q") (pintype "output"))
      (node (ref "GATE63") (pin "B") (pinfunction "B_B") (pintype "input"))
    )
    (net (code "15") (name "31DAY{slash}") (class "Default")
      (node (ref "GATE107") (pin "Q") (pinfunction "Q_Q") (pintype "output"))
      (node (ref "GATE66") (pin "B") (pinfunction "B_B") (pintype "input"))
    )
    (net (code "16") (name "AC_CLK{slash}") (class "Default")
      (node (ref "A_BUS") (pin "33") (pinfunction "33_33") (pintype "passive"))
      (node (ref "GATE130") (pin "B") (pinfunction "B_B") (pintype "input"))
      (node (ref "GATE146") (pin "A") (pinfunction "A_A") (pintype "input"))
      (node (ref "GATE27") (pin "B") (pinfunction "B_B") (pintype "input"))
      (node (ref "GATE49") (pin "A") (pinfunction "A_A") (pintype "input"))
      (node (ref "GATE95") (pin "B") (pinfunction "B_B") (pintype "input"))
    )
    (net (code "17") (name "DOM_SET_BTN") (class "Default")
      (node (ref "GATE145") (pin "B") (pinfunction "B_B") (pintype "input"))
      (node (ref "GATE32") (pin "C") (pinfunction "C_C") (pintype "input"))
      (node (ref "GATE50") (pin "A") (pinfunction "A_A") (pintype "input"))
      (node (ref "Q1") (pin "3") (pinfunction "D_3") (pintype "passive"))
      (node (ref "R3") (pin "1") (pinfunction "1_1") (pintype "passive"))
    )
    (net (code "18") (name "DOM_TENS_A") (class "Default")
      (node (ref "B_BUS") (pin "8") (pinfunction "8_8") (pintype "passive"))
      (node (ref "GATE37") (pin "Q") (pinfunction "Q_Q") (pintype "output"))
      (node (ref "GATE38") (pin "A") (pinfunction "A_A") (pintype "input"))
      (node (ref "GATE40") (pin "B") (pinfunction "B_B") (pintype "input"))
      (node (ref "GATE41") (pin "B") (pinfunction "B_B") (pintype "input"))
    )
    (net (code "19") (name "DOM_TENS_B") (class "Default")
      (node (ref "B_BUS") (pin "9") (pinfunction "9_9") (pintype "passive"))
      (node (ref "GATE43") (pin "Q") (pinfunction "Q_Q") (pintype "output"))
      (node (ref "GATE44") (pin "A") (pinfunction "A_A") (pintype "input"))
    )
    (net (code "20") (name "DOM_UNIT_A") (class "Default")
      (node (ref "B_BUS") (pin "4") (pinfunction "4_4") (pintype "passive"))
      (node (ref "GATE5") (pin "Q") (pinfunction "Q_Q") (pintype "output"))
      (node (ref "GATE58") (pin "A") (pinfunction "A_A") (pintype "input"))
      (node (ref "GATE6") (pin "A") (pinfunction "A_A") (pintype "input"))
      (node (ref "GATE8") (pin "B") (pinfunction "B_B") (pintype "input"))
      (node (ref "GATE9") (pin "B") (pinfunction "B_B") (pintype "input"))
    )
    (net (code "21") (name "DOM_UNIT_B") (class "Default")
      (node (ref "B_BUS") (pin "5") (pinfunction "5_5") (pintype "passive"))
      (node (ref "GATE11") (pin "Q") (pinfunction "Q_Q") (pintype "output"))
      (node (ref "GATE12") (pin "A") (pinfunction "A_A") (pintype "input"))
      (node (ref "GATE14") (pin "B") (pinfunction "B_B") (pintype "input"))
      (node (ref "GATE15") (pin "B") (pinfunction "B_B") (pintype "input"))
    )
    (net (code "22") (name "DOM_UNIT_C") (class "Default")
      (node (ref "B_BUS") (pin "6") (pinfunction "6_6") (pintype "passive"))
      (node (ref "GATE17") (pin "Q") (pinfunction "Q_Q") (pintype "output"))
      (node (ref "GATE18") (pin "A") (pinfunction "A_A") (pintype "input"))
      (node (ref "GATE20") (pin "B") (pinfunction "B_B") (pintype "input"))
      (node (ref "GATE21") (pin "B") (pinfunction "B_B") (pintype "input"))
      (node (ref "GATE58") (pin "B") (pinfunction "B_B") (pintype "input"))
    )
    (net (code "23") (name "DOM_UNIT_D") (class "Default")
      (node (ref "B_BUS") (pin "7") (pinfunction "7_7") (pintype "passive"))
      (node (ref "GATE23") (pin "Q") (pinfunction "Q_Q") (pintype "output"))
      (node (ref "GATE24") (pin "A") (pinfunction "A_A") (pintype "input"))
      (node (ref "GATE58") (pin "C") (pinfunction "C_C") (pintype "input"))
    )
    (net (code "24") (name "DOW_A") (class "Default")
      (node (ref "B_BUS") (pin "1") (pinfunction "1_1") (pintype "passive"))
      (node (ref "GATE114") (pin "Q") (pinfunction "Q_Q") (pintype "output"))
      (node (ref "GATE115") (pin "A") (pinfunction "A_A") (pintype "input"))
      (node (ref "GATE117") (pin "B") (pinfunction "B_B") (pintype "input"))
      (node (ref "GATE118") (pin "B") (pinfunction "B_B") (pintype "input"))
    )
    (net (code "25") (name "DOW_B") (class "Default")
      (node (ref "B_BUS") (pin "2") (pinfunction "2_2") (pintype "passive"))
      (node (ref "GATE120") (pin "Q") (pinfunction "Q_Q") (pintype "output"))
      (node (ref "GATE121") (pin "A") (pinfunction "A_A") (pintype "input"))
      (node (ref "GATE123") (pin "B") (pinfunction "B_B") (pintype "input"))
      (node (ref "GATE124") (pin "B") (pinfunction "B_B") (pintype "input"))
    )
    (net (code "26") (name "DOW_C") (class "Default")
      (node (ref "B_BUS") (pin "3") (pinfunction "3_3") (pintype "passive"))
      (node (ref "GATE126") (pin "Q") (pinfunction "Q_Q") (pintype "output"))
      (node (ref "GATE127") (pin "A") (pinfunction "A_A") (pintype "input"))
    )
    (net (code "27") (name "DOW_SET_BTN") (class "Default")
      (node (ref "GATE134") (pin "B") (pinfunction "B_B") (pintype "input"))
      (node (ref "Q3") (pin "3") (pinfunction "D_3") (pintype "passive"))
      (node (ref "R9") (pin "1") (pinfunction "1_1") (pintype "passive"))
    )
    (net (code "28") (name "FEB{slash}") (class "Default")
      (node (ref "GATE101") (pin "Q") (pinfunction "Q_Q") (pintype "output"))
      (node (ref "GATE57") (pin "B") (pinfunction "B_B") (pintype "input"))
      (node (ref "GATE60") (pin "B") (pinfunction "B_B") (pintype "input"))
    )
    (net (code "29") (name "LEAP_SET_BTN") (class "Default")
      (node (ref "GATE136") (pin "B") (pinfunction "B_B") (pintype "input"))
      (node (ref "GATE137") (pin "B") (pinfunction "B_B") (pintype "input"))
      (node (ref "Q4") (pin "3") (pinfunction "D_3") (pintype "passive"))
      (node (ref "R12") (pin "1") (pinfunction "1_1") (pintype "passive"))
    )
    (net (code "30") (name "LEAP_YEAR") (class "Default")
      (node (ref "A_BUS") (pin "28") (pinfunction "28_28") (pintype "passive"))
      (node (ref "GATE139") (pin "Q") (pinfunction "Q_Q") (pintype "output"))
      (node (ref "GATE140") (pin "A") (pinfunction "A_A") (pintype "input"))
      (node (ref "GATE57") (pin "C") (pinfunction "C_C") (pintype "input"))
    )
    (net (code "31") (name "LEAP_YEAR{slash}") (class "Default")
      (node (ref "GATE138") (pin "B") (pinfunction "B_B") (pintype "input"))
      (node (ref "GATE139") (pin "B") (pinfunction "B_B") (pintype "input"))
      (node (ref "GATE140") (pin "Q") (pinfunction "Q_Q") (pintype "output"))
      (node (ref "GATE60") (pin "C") (pinfunction "C_C") (pintype "input"))
    )
    (net (code "32") (name "MCLR") (class "Default")
      (node (ref "A_BUS") (pin "35") (pinfunction "35_35") (pintype "passive"))
      (node (ref "GATE131") (pin "B") (pinfunction "B_B") (pintype "input"))
      (node (ref "GATE134") (pin "A") (pinfunction "A_A") (pintype "input"))
      (node (ref "GATE141") (pin "B") (pinfunction "B_B") (pintype "input"))
      (node (ref "GATE143") (pin "A") (pinfunction "A_A") (pintype "input"))
      (node (ref "GATE147") (pin "A") (pinfunction "A_A") (pintype "input"))
      (node (ref "GATE28") (pin "B") (pinfunction "B_B") (pintype "input"))
      (node (ref "GATE32") (pin "B") (pinfunction "B_B") (pintype "input"))
      (node (ref "GATE47") (pin "B") (pinfunction "B_B") (pintype "input"))
      (node (ref "GATE52") (pin "A") (pinfunction "A_A") (pintype "input"))
      (node (ref "GATE96") (pin "B") (pinfunction "B_B") (pintype "input"))
      (node (ref "GATE99") (pin "A") (pinfunction "A_A") (pintype "input"))
    )
    (net (code "33") (name "MON_A") (class "Default")
      (node (ref "B_BUS") (pin "10") (pinfunction "10_10") (pintype "passive"))
      (node (ref "GATE104") (pin "A") (pinfunction "A_A") (pintype "input"))
      (node (ref "GATE106") (pin "A") (pinfunction "A_A") (pintype "input"))
      (node (ref "GATE73") (pin "Q") (pinfunction "Q_Q") (pintype "output"))
      (node (ref "GATE74") (pin "A") (pinfunction "A_A") (pintype "input"))
      (node (ref "GATE76") (pin "B") (pinfunction "B_B") (pintype "input"))
      (node (ref "GATE77") (pin "B") (pinfunction "B_B") (pintype "input"))
    )
    (net (code "34") (name "MON_B") (class "Default")
      (node (ref "B_BUS") (pin "11") (pinfunction "11_11") (pintype "passive"))
      (node (ref "GATE100") (pin "B") (pinfunction "B_B") (pintype "input"))
      (node (ref "GATE102") (pin "B") (pinfunction "B_B") (pintype "input"))
      (node (ref "GATE79") (pin "Q") (pinfunction "Q_Q") (pintype "output"))
      (node (ref "GATE80") (pin "A") (pinfunction "A_A") (pintype "input"))
      (node (ref "GATE82") (pin "B") (pinfunction "B_B") (pintype "input"))
      (node (ref "GATE83") (pin "B") (pinfunction "B_B") (pintype "input"))
    )
    (net (code "35") (name "MON_C") (class "Default")
      (node (ref "B_BUS") (pin "12") (pinfunction "12_12") (pintype "passive"))
      (node (ref "GATE100") (pin "C") (pinfunction "C_C") (pintype "input"))
      (node (ref "GATE104") (pin "B") (pinfunction "B_B") (pintype "input"))
      (node (ref "GATE105") (pin "C") (pinfunction "C_C") (pintype "input"))
      (node (ref "GATE108") (pin "B") (pinfunction "B_B") (pintype "input"))
      (node (ref "GATE85") (pin "Q") (pinfunction "Q_Q") (pintype "output"))
      (node (ref "GATE86") (pin "A") (pinfunction "A_A") (pintype "input"))
      (node (ref "GATE88") (pin "B") (pinfunction "B_B") (pintype "input"))
      (node (ref "GATE89") (pin "B") (pinfunction "B_B") (pintype "input"))
    )
    (net (code "36") (name "MON_D") (class "Default")
      (node (ref "B_BUS") (pin "13") (pinfunction "13_13") (pintype "passive"))
      (node (ref "GATE100") (pin "D") (pinfunction "D_D") (pintype "input"))
      (node (ref "GATE102") (pin "D") (pinfunction "D_D") (pintype "input"))
      (node (ref "GATE105") (pin "D") (pinfunction "D_D") (pintype "input"))
      (node (ref "GATE106") (pin "B") (pinfunction "B_B") (pintype "input"))
      (node (ref "GATE109") (pin "C") (pinfunction "C_C") (pintype "input"))
      (node (ref "GATE91") (pin "Q") (pinfunction "Q_Q") (pintype "output"))
      (node (ref "GATE92") (pin "A") (pinfunction "A_A") (pintype "input"))
    )
    (net (code "37") (name "MON_RST") (class "Default")
      (node (ref "GATE141") (pin "A") (pinfunction "A_A") (pintype "input"))
      (node (ref "GATE69") (pin "A") (pinfunction "A_A") (pintype "input"))
      (node (ref "GATE75") (pin "A") (pinfunction "A_A") (pintype "input"))
      (node (ref "GATE81") (pin "A") (pinfunction "A_A") (pintype "input"))
      (node (ref "GATE87") (pin "A") (pinfunction "A_A") (pintype "input"))
      (node (ref "GATE97") (pin "Q") (pinfunction "Q_Q") (pintype "output"))
    )
    (net (code "38") (name "MON_SET_BTN") (class "Default")
      (node (ref "GATE99") (pin "B") (pinfunction "B_B") (pintype "input"))
      (node (ref "Q2") (pin "3") (pinfunction "D_3") (pintype "passive"))
      (node (ref "R6") (pin "1") (pinfunction "1_1") (pintype "passive"))
    )
    (net (code "39") (name "Net-(C2-Pad1)") (class "Default")
      (node (ref "C2") (pin "1") (pinfunction "1_1") (pintype "passive"))
      (node (ref "GATE148") (pin "B") (pinfunction "B_B") (pintype "input"))
      (node (ref "GATE149") (pin "Q") (pinfunction "Q_Q") (pintype "output"))
      (node (ref "GATE2") (pin "B") (pinfunction "B_B") (pintype "input"))
    )
    (net (code "40") (name "Net-(C3-Pad1)") (class "Default")
      (node (ref "C3") (pin "1") (pinfunction "1_1") (pintype "passive"))
      (node (ref "GATE143") (pin "B") (pinfunction "B_B") (pintype "input"))
      (node (ref "GATE145") (pin "Q") (pinfunction "Q_Q") (pintype "output"))
      (node (ref "GATE28") (pin "C") (pinfunction "C_C") (pintype "input"))
      (node (ref "GATE32") (pin "A") (pinfunction "A_A") (pintype "input"))
      (node (ref "GATE45") (pin "A") (pinfunction "A_A") (pintype "input"))
      (node (ref "GATE52") (pin "B") (pinfunction "B_B") (pintype "input"))
    )
    (net (code "41") (name "Net-(GATE1-PadB)") (class "Default")
      (node (ref "GATE1") (pin "B") (pinfunction "B_B") (pintype "input"))
      (node (ref "GATE3") (pin "C") (pinfunction "C_C") (pintype "input"))
      (node (ref "GATE4") (pin "Q") (pinfunction "Q_Q") (pintype "output"))
    )
    (net (code "42") (name "Net-(GATE1-PadC)") (class "Default")
      (node (ref "GATE1") (pin "C") (pinfunction "C_C") (pintype "input"))
      (node (ref "GATE2") (pin "Q") (pinfunction "Q_Q") (pintype "output"))
      (node (ref "GATE3") (pin "A") (pinfunction "A_A") (pintype "input"))
      (node (ref "GATE5") (pin "A") (pinfunction "A_A") (pintype "input"))
    )
    (net (code "43") (name "Net-(GATE1-PadQ)") (class "Default")
      (node (ref "GATE1") (pin "Q") (pinfunction "Q_Q") (pintype "output"))
      (node (ref "GATE2") (pin "A") (pinfunction "A_A") (pintype "input"))
    )
    (net (code "44") (name "Net-(GATE2-PadC)") (class "Default")
      (node (ref "GATE2") (pin "C") (pinfunction "C_C") (pintype "input"))
      (node (ref "GATE3") (pin "B") (pinfunction "B_B") (pintype "input"))
      (node (ref "GATE32") (pin "Q") (pinfunction "Q_Q") (pintype "output"))
    )
    (net (code "45") (name "Net-(GATE3-PadQ)") (class "Default")
      (node (ref "GATE3") (pin "Q") (pinfunction "Q_Q") (pintype "output"))
      (node (ref "GATE4") (pin "A") (pinfunction "A_A") (pintype "input"))
      (node (ref "GATE6") (pin "B") (pinfunction "B_B") (pintype "input"))
    )
    (net (code "46") (name "Net-(GATE4-PadB)") (class "Default")
      (node (ref "GATE4") (pin "B") (pinfunction "B_B") (pintype "input"))
      (node (ref "GATE5") (pin "B") (pinfunction "B_B") (pintype "input"))
      (node (ref "GATE55") (pin "A") (pinfunction "A_A") (pintype "input"))
      (node (ref "GATE6") (pin "Q") (pinfunction "Q_Q") (pintype "output"))
      (node (ref "GATE61") (pin "A") (pinfunction "A_A") (pintype "input"))
    )
    (net (code "47") (name "Net-(GATE7-PadQ)") (class "Default")
      (node (ref "GATE7") (pin "Q") (pinfunction "Q_Q") (pintype "output"))
      (node (ref "GATE8") (pin "A") (pinfunction "A_A") (pintype "input"))
    )
    (net (code "48") (name "Net-(GATE10-PadA)") (class "Default")
      (node (ref "GATE10") (pin "A") (pinfunction "A_A") (pintype "input"))
      (node (ref "GATE12") (pin "B") (pinfunction "B_B") (pintype "input"))
      (node (ref "GATE9") (pin "Q") (pinfunction "Q_Q") (pintype "output"))
    )
    (net (code "49") (name "Net-(GATE10-PadB)") (class "Default")
      (node (ref "GATE10") (pin "B") (pinfunction "B_B") (pintype "input"))
      (node (ref "GATE11") (pin "B") (pinfunction "B_B") (pintype "input"))
      (node (ref "GATE12") (pin "Q") (pinfunction "Q_Q") (pintype "output"))
      (node (ref "GATE25") (pin "B") (pinfunction "B_B") (pintype "input"))
      (node (ref "GATE64") (pin "A") (pinfunction "A_A") (pintype "input"))
    )
    (net (code "50") (name "Net-(GATE10-PadQ)") (class "Default")
      (node (ref "GATE10") (pin "Q") (pinfunction "Q_Q") (pintype "output"))
      (node (ref "GATE7") (pin "B") (pinfunction "B_B") (pintype "input"))
      (node (ref "GATE9") (pin "C") (pinfunction "C_C") (pintype "input"))
    )
    (net (code "51") (name "Net-(GATE11-PadA)") (class "Default")
      (node (ref "GATE11") (pin "A") (pinfunction "A_A") (pintype "input"))
      (node (ref "GATE7") (pin "C") (pinfunction "C_C") (pintype "input"))
      (node (ref "GATE8") (pin "Q") (pinfunction "Q_Q") (pintype "output"))
      (node (ref "GATE9") (pin "A") (pinfunction "A_A") (pintype "input"))
    )
    (net (code "52") (name "Net-(GATE13-PadB)") (class "Default")
      (node (ref "GATE13") (pin "B") (pinfunction "B_B") (pintype "input"))
      (node (ref "GATE15") (pin "C") (pinfunction "C_C") (pintype "input"))
      (node (ref "GATE16") (pin "Q") (pinfunction "Q_Q") (pintype "output"))
    )
    (net (code "53") (name "Net-(GATE13-PadC)") (class "Default")
      (node (ref "GATE13") (pin "C") (pinfunction "C_C") (pintype "input"))
      (node (ref "GATE14") (pin "Q") (pinfunction "Q_Q") (pintype "output"))
      (node (ref "GATE15") (pin "A") (pinfunction "A_A") (pintype "input"))
      (node (ref "GATE17") (pin "A") (pinfunction "A_A") (pintype "input"))
    )
    (net (code "54") (name "Net-(GATE13-PadQ)") (class "Default")
      (node (ref "GATE13") (pin "Q") (pinfunction "Q_Q") (pintype "output"))
      (node (ref "GATE14") (pin "A") (pinfunction "A_A") (pintype "input"))
    )
    (net (code "55") (name "Net-(GATE15-PadQ)") (class "Default")
      (node (ref "GATE15") (pin "Q") (pinfunction "Q_Q") (pintype "output"))
      (node (ref "GATE16") (pin "A") (pinfunction "A_A") (pintype "input"))
      (node (ref "GATE18") (pin "B") (pinfunction "B_B") (pintype "input"))
    )
    (net (code "56") (name "Net-(GATE16-PadB)") (class "Default")
      (node (ref "GATE16") (pin "B") (pinfunction "B_B") (pintype "input"))
      (node (ref "GATE17") (pin "B") (pinfunction "B_B") (pintype "input"))
      (node (ref "GATE18") (pin "Q") (pinfunction "Q_Q") (pintype "output"))
    )
    (net (code "57") (name "Net-(GATE19-PadB)") (class "Default")
      (node (ref "GATE19") (pin "B") (pinfunction "B_B") (pintype "input"))
      (node (ref "GATE21") (pin "C") (pinfunction "C_C") (pintype "input"))
      (node (ref "GATE22") (pin "Q") (pinfunction "Q_Q") (pintype "output"))
    )
    (net (code "58") (name "Net-(GATE19-PadC)") (class "Default")
      (node (ref "GATE19") (pin "C") (pinfunction "C_C") (pintype "input"))
      (node (ref "GATE20") (pin "Q") (pinfunction "Q_Q") (pintype "output"))
      (node (ref "GATE21") (pin "A") (pinfunction "A_A") (pintype "input"))
      (node (ref "GATE23") (pin "A") (pinfunction "A_A") (pintype "input"))
    )
    (net (code "59") (name "Net-(GATE19-PadQ)") (class "Default")
      (node (ref "GATE19") (pin "Q") (pinfunction "Q_Q") (pintype "output"))
      (node (ref "GATE20") (pin "A") (pinfunction "A_A") (pintype "input"))
    )
    (net (code "60") (name "Net-(GATE21-PadQ)") (class "Default")
      (node (ref "GATE21") (pin "Q") (pinfunction "Q_Q") (pintype "output"))
      (node (ref "GATE22") (pin "A") (pinfunction "A_A") (pintype "input"))
      (node (ref "GATE24") (pin "B") (pinfunction "B_B") (pintype "input"))
    )
    (net (code "61") (name "Net-(GATE22-PadB)") (class "Default")
      (node (ref "GATE22") (pin "B") (pinfunction "B_B") (pintype "input"))
      (node (ref "GATE23") (pin "B") (pinfunction "B_B") (pintype "input"))
      (node (ref "GATE24") (pin "Q") (pinfunction "Q_Q") (pintype "output"))
      (node (ref "GATE25") (pin "A") (pinfunction "A_A") (pintype "input"))
      (node (ref "GATE55") (pin "B") (pinfunction "B_B") (pintype "input"))
    )
    (net (code "62") (name "Net-(GATE25-PadQ)") (class "Default")
      (node (ref "GATE25") (pin "Q") (pinfunction "Q_Q") (pintype "output"))
      (node (ref "GATE26") (pin "A") (pinfunction "A_A") (pintype "input"))
    )
    (net (code "63") (name "Net-(GATE26-PadB)") (class "Default")
      (node (ref "GATE26") (pin "B") (pinfunction "B_B") (pintype "input"))
      (node (ref "GATE27") (pin "Q") (pinfunction "Q_Q") (pintype "output"))
      (node (ref "GATE28") (pin "A") (pinfunction "A_A") (pintype "input"))
    )
    (net (code "64") (name "Net-(GATE26-PadQ)") (class "Default")
      (node (ref "GATE26") (pin "Q") (pinfunction "Q_Q") (pintype "output"))
      (node (ref "GATE27") (pin "A") (pinfunction "A_A") (pintype "input"))
      (node (ref "GATE51") (pin "A") (pinfunction "A_A") (pintype "input"))
    )
    (net (code "65") (name "Net-(GATE28-PadQ)") (class "Default")
      (node (ref "GATE28") (pin "Q") (pinfunction "Q_Q") (pintype "output"))
      (node (ref "GATE29") (pin "A") (pinfunction "A_A") (pintype "input"))
    )
    (net (code "66") (name "Net-(GATE31-PadQ)") (class "Default")
      (node (ref "GATE31") (pin "Q") (pinfunction "Q_Q") (pintype "output"))
      (node (ref "GATE32") (pin "D") (pinfunction "D_D") (pintype "input"))
    )
    (net (code "67") (name "Net-(GATE33-PadB)") (class "Default")
      (node (ref "GATE33") (pin "B") (pinfunction "B_B") (pintype "input"))
      (node (ref "GATE35") (pin "C") (pinfunction "C_C") (pintype "input"))
      (node (ref "GATE36") (pin "Q") (pinfunction "Q_Q") (pintype "output"))
    )
    (net (code "68") (name "Net-(GATE33-PadC)") (class "Default")
      (node (ref "GATE33") (pin "C") (pinfunction "C_C") (pintype "input"))
      (node (ref "GATE34") (pin "Q") (pinfunction "Q_Q") (pintype "output"))
      (node (ref "GATE35") (pin "A") (pinfunction "A_A") (pintype "input"))
      (node (ref "GATE37") (pin "A") (pinfunction "A_A") (pintype "input"))
    )
    (net (code "69") (name "Net-(GATE33-PadQ)") (class "Default")
      (node (ref "GATE33") (pin "Q") (pinfunction "Q_Q") (pintype "output"))
      (node (ref "GATE34") (pin "A") (pinfunction "A_A") (pintype "input"))
    )
    (net (code "70") (name "Net-(GATE34-PadB)") (class "Default")
      (node (ref "GATE34") (pin "B") (pinfunction "B_B") (pintype "input"))
      (node (ref "GATE35") (pin "B") (pinfunction "B_B") (pintype "input"))
      (node (ref "GATE52") (pin "Q") (pinfunction "Q_Q") (pintype "output"))
    )
    (net (code "71") (name "Net-(GATE35-PadQ)") (class "Default")
      (node (ref "GATE35") (pin "Q") (pinfunction "Q_Q") (pintype "output"))
      (node (ref "GATE36") (pin "A") (pinfunction "A_A") (pintype "input"))
      (node (ref "GATE38") (pin "B") (pinfunction "B_B") (pintype "input"))
    )
    (net (code "72") (name "Net-(GATE36-PadB)") (class "Default")
      (node (ref "GATE36") (pin "B") (pinfunction "B_B") (pintype "input"))
      (node (ref "GATE37") (pin "B") (pinfunction "B_B") (pintype "input"))
      (node (ref "GATE38") (pin "Q") (pinfunction "Q_Q") (pintype "output"))
      (node (ref "GATE53") (pin "B") (pinfunction "B_B") (pintype "input"))
    )
    (net (code "73") (name "Net-(GATE39-PadB)") (class "Default")
      (node (ref "GATE39") (pin "B") (pinfunction "B_B") (pintype "input"))
      (node (ref "GATE41") (pin "C") (pinfunction "C_C") (pintype "input"))
      (node (ref "GATE42") (pin "Q") (pinfunction "Q_Q") (pintype "output"))
    )
    (net (code "74") (name "Net-(GATE39-PadC)") (class "Default")
      (node (ref "GATE39") (pin "C") (pinfunction "C_C") (pintype "input"))
      (node (ref "GATE40") (pin "Q") (pinfunction "Q_Q") (pintype "output"))
      (node (ref "GATE41") (pin "A") (pinfunction "A_A") (pintype "input"))
      (node (ref "GATE43") (pin "A") (pinfunction "A_A") (pintype "input"))
    )
    (net (code "75") (name "Net-(GATE39-PadQ)") (class "Default")
      (node (ref "GATE39") (pin "Q") (pinfunction "Q_Q") (pintype "output"))
      (node (ref "GATE40") (pin "A") (pinfunction "A_A") (pintype "input"))
    )
    (net (code "76") (name "Net-(GATE41-PadQ)") (class "Default")
      (node (ref "GATE41") (pin "Q") (pinfunction "Q_Q") (pintype "output"))
      (node (ref "GATE42") (pin "A") (pinfunction "A_A") (pintype "input"))
      (node (ref "GATE44") (pin "B") (pinfunction "B_B") (pintype "input"))
    )
    (net (code "77") (name "Net-(GATE42-PadB)") (class "Default")
      (node (ref "GATE42") (pin "B") (pinfunction "B_B") (pintype "input"))
      (node (ref "GATE43") (pin "B") (pinfunction "B_B") (pintype "input"))
      (node (ref "GATE44") (pin "Q") (pinfunction "Q_Q") (pintype "output"))
      (node (ref "GATE53") (pin "A") (pinfunction "A_A") (pintype "input"))
      (node (ref "GATE55") (pin "C") (pinfunction "C_C") (pintype "input"))
    )
    (net (code "78") (name "Net-(GATE45-PadB)") (class "Default")
      (node (ref "GATE45") (pin "B") (pinfunction "B_B") (pintype "input"))
      (node (ref "GATE46") (pin "Q") (pinfunction "Q_Q") (pintype "output"))
      (node (ref "GATE47") (pin "A") (pinfunction "A_A") (pintype "input"))
    )
    (net (code "79") (name "Net-(GATE46-PadB)") (class "Default")
      (node (ref "GATE46") (pin "B") (pinfunction "B_B") (pintype "input"))
      (node (ref "GATE50") (pin "Q") (pinfunction "Q_Q") (pintype "output"))
    )
    (net (code "80") (name "Net-(GATE47-PadQ)") (class "Default")
      (node (ref "GATE47") (pin "Q") (pinfunction "Q_Q") (pintype "output"))
      (node (ref "GATE48") (pin "A") (pinfunction "A_A") (pintype "input"))
    )
    (net (code "81") (name "Net-(GATE49-PadQ)") (class "Default")
      (node (ref "GATE49") (pin "Q") (pinfunction "Q_Q") (pintype "output"))
      (node (ref "GATE50") (pin "B") (pinfunction "B_B") (pintype "input"))
    )
    (net (code "82") (name "Net-(GATE51-PadQ)") (class "Default")
      (node (ref "GATE51") (pin "Q") (pinfunction "Q_Q") (pintype "output"))
      (node (ref "GATE52") (pin "C") (pinfunction "C_C") (pintype "input"))
    )
    (net (code "83") (name "Net-(GATE53-PadQ)") (class "Default")
      (node (ref "GATE53") (pin "Q") (pinfunction "Q_Q") (pintype "output"))
      (node (ref "GATE54") (pin "A") (pinfunction "A_A") (pintype "input"))
    )
    (net (code "84") (name "Net-(GATE54-PadQ)") (class "Default")
      (node (ref "GATE54") (pin "Q") (pinfunction "Q_Q") (pintype "output"))
      (node (ref "GATE58") (pin "D") (pinfunction "D_D") (pintype "input"))
      (node (ref "GATE61") (pin "B") (pinfunction "B_B") (pintype "input"))
      (node (ref "GATE64") (pin "B") (pinfunction "B_B") (pintype "input"))
    )
    (net (code "85") (name "Net-(GATE55-PadQ)") (class "Default")
      (node (ref "GATE55") (pin "Q") (pinfunction "Q_Q") (pintype "output"))
      (node (ref "GATE56") (pin "A") (pinfunction "A_A") (pintype "input"))
    )
    (net (code "86") (name "Net-(GATE57-PadQ)") (class "Default")
      (node (ref "GATE57") (pin "Q") (pinfunction "Q_Q") (pintype "output"))
      (node (ref "GATE67") (pin "A") (pinfunction "A_A") (pintype "input"))
    )
    (net (code "87") (name "Net-(GATE58-PadQ)") (class "Default")
      (node (ref "GATE58") (pin "Q") (pinfunction "Q_Q") (pintype "output"))
      (node (ref "GATE59") (pin "A") (pinfunction "A_A") (pintype "input"))
    )
    (net (code "88") (name "Net-(GATE60-PadQ)") (class "Default")
      (node (ref "GATE60") (pin "Q") (pinfunction "Q_Q") (pintype "output"))
      (node (ref "GATE67") (pin "B") (pinfunction "B_B") (pintype "input"))
    )
    (net (code "89") (name "Net-(GATE61-PadQ)") (class "Default")
      (node (ref "GATE61") (pin "Q") (pinfunction "Q_Q") (pintype "output"))
      (node (ref "GATE62") (pin "A") (pinfunction "A_A") (pintype "input"))
    )
    (net (code "90") (name "Net-(GATE63-PadQ)") (class "Default")
      (node (ref "GATE63") (pin "Q") (pinfunction "Q_Q") (pintype "output"))
      (node (ref "GATE67") (pin "C") (pinfunction "C_C") (pintype "input"))
    )
    (net (code "91") (name "Net-(GATE64-PadQ)") (class "Default")
      (node (ref "GATE64") (pin "Q") (pinfunction "Q_Q") (pintype "output"))
      (node (ref "GATE65") (pin "A") (pinfunction "A_A") (pintype "input"))
    )
    (net (code "92") (name "Net-(GATE66-PadQ)") (class "Default")
      (node (ref "GATE66") (pin "Q") (pinfunction "Q_Q") (pintype "output"))
      (node (ref "GATE67") (pin "D") (pinfunction "D_D") (pintype "input"))
    )
    (net (code "93") (name "Net-(GATE67-PadQ)") (class "Default")
      (node (ref "GATE67") (pin "Q") (pinfunction "Q_Q") (pintype "output"))
      (node (ref "GATE68") (pin "A") (pinfunction "A_A") (pintype "input"))
    )
    (net (code "94") (name "Net-(GATE69-PadB)") (class "Default")
      (node (ref "GATE69") (pin "B") (pinfunction "B_B") (pintype "input"))
      (node (ref "GATE71") (pin "C") (pinfunction "C_C") (pintype "input"))
      (node (ref "GATE72") (pin "Q") (pinfunction "Q_Q") (pintype "output"))
    )
    (net (code "95") (name "Net-(GATE69-PadC)") (class "Default")
      (node (ref "GATE69") (pin "C") (pinfunction "C_C") (pintype "input"))
      (node (ref "GATE70") (pin "Q") (pinfunction "Q_Q") (pintype "output"))
      (node (ref "GATE71") (pin "A") (pinfunction "A_A") (pintype "input"))
      (node (ref "GATE73") (pin "A") (pinfunction "A_A") (pintype "input"))
    )
    (net (code "96") (name "Net-(GATE69-PadQ)") (class "Default")
      (node (ref "GATE69") (pin "Q") (pinfunction "Q_Q") (pintype "output"))
      (node (ref "GATE70") (pin "A") (pinfunction "A_A") (pintype "input"))
    )
    (net (code "97") (name "Net-(GATE70-PadB)") (class "Default")
      (node (ref "GATE70") (pin "B") (pinfunction "B_B") (pintype "input"))
      (node (ref "GATE71") (pin "B") (pinfunction "B_B") (pintype "input"))
      (node (ref "GATE99") (pin "Q") (pinfunction "Q_Q") (pintype "output"))
    )
    (net (code "98") (name "Net-(GATE71-PadQ)") (class "Default")
      (node (ref "GATE71") (pin "Q") (pinfunction "Q_Q") (pintype "output"))
      (node (ref "GATE72") (pin "A") (pinfunction "A_A") (pintype "input"))
      (node (ref "GATE74") (pin "B") (pinfunction "B_B") (pintype "input"))
    )
    (net (code "99") (name "Net-(GATE75-PadB)") (class "Default")
      (node (ref "GATE75") (pin "B") (pinfunction "B_B") (pintype "input"))
      (node (ref "GATE77") (pin "C") (pinfunction "C_C") (pintype "input"))
      (node (ref "GATE78") (pin "Q") (pinfunction "Q_Q") (pintype "output"))
    )
    (net (code "100") (name "Net-(GATE75-PadC)") (class "Default")
      (node (ref "GATE75") (pin "C") (pinfunction "C_C") (pintype "input"))
      (node (ref "GATE76") (pin "Q") (pinfunction "Q_Q") (pintype "output"))
      (node (ref "GATE77") (pin "A") (pinfunction "A_A") (pintype "input"))
      (node (ref "GATE79") (pin "A") (pinfunction "A_A") (pintype "input"))
    )
    (net (code "101") (name "Net-(GATE75-PadQ)") (class "Default")
      (node (ref "GATE75") (pin "Q") (pinfunction "Q_Q") (pintype "output"))
      (node (ref "GATE76") (pin "A") (pinfunction "A_A") (pintype "input"))
    )
    (net (code "102") (name "Net-(GATE77-PadQ)") (class "Default")
      (node (ref "GATE77") (pin "Q") (pinfunction "Q_Q") (pintype "output"))
      (node (ref "GATE78") (pin "A") (pinfunction "A_A") (pintype "input"))
      (node (ref "GATE80") (pin "B") (pinfunction "B_B") (pintype "input"))
    )
    (net (code "103") (name "Net-(GATE81-PadB)") (class "Default")
      (node (ref "GATE81") (pin "B") (pinfunction "B_B") (pintype "input"))
      (node (ref "GATE83") (pin "C") (pinfunction "C_C") (pintype "input"))
      (node (ref "GATE84") (pin "Q") (pinfunction "Q_Q") (pintype "output"))
    )
    (net (code "104") (name "Net-(GATE81-PadC)") (class "Default")
      (node (ref "GATE81") (pin "C") (pinfunction "C_C") (pintype "input"))
      (node (ref "GATE82") (pin "Q") (pinfunction "Q_Q") (pintype "output"))
      (node (ref "GATE83") (pin "A") (pinfunction "A_A") (pintype "input"))
      (node (ref "GATE85") (pin "A") (pinfunction "A_A") (pintype "input"))
    )
    (net (code "105") (name "Net-(GATE81-PadQ)") (class "Default")
      (node (ref "GATE81") (pin "Q") (pinfunction "Q_Q") (pintype "output"))
      (node (ref "GATE82") (pin "A") (pinfunction "A_A") (pintype "input"))
    )
    (net (code "106") (name "Net-(GATE83-PadQ)") (class "Default")
      (node (ref "GATE83") (pin "Q") (pinfunction "Q_Q") (pintype "output"))
      (node (ref "GATE84") (pin "A") (pinfunction "A_A") (pintype "input"))
      (node (ref "GATE86") (pin "B") (pinfunction "B_B") (pintype "input"))
    )
    (net (code "107") (name "Net-(GATE87-PadB)") (class "Default")
      (node (ref "GATE87") (pin "B") (pinfunction "B_B") (pintype "input"))
      (node (ref "GATE89") (pin "C") (pinfunction "C_C") (pintype "input"))
      (node (ref "GATE90") (pin "Q") (pinfunction "Q_Q") (pintype "output"))
    )
    (net (code "108") (name "Net-(GATE87-PadC)") (class "Default")
      (node (ref "GATE87") (pin "C") (pinfunction "C_C") (pintype "input"))
      (node (ref "GATE88") (pin "Q") (pinfunction "Q_Q") (pintype "output"))
      (node (ref "GATE89") (pin "A") (pinfunction "A_A") (pintype "input"))
      (node (ref "GATE91") (pin "A") (pinfunction "A_A") (pintype "input"))
    )
    (net (code "109") (name "Net-(GATE87-PadQ)") (class "Default")
      (node (ref "GATE87") (pin "Q") (pinfunction "Q_Q") (pintype "output"))
      (node (ref "GATE88") (pin "A") (pinfunction "A_A") (pintype "input"))
    )
    (net (code "110") (name "Net-(GATE89-PadQ)") (class "Default")
      (node (ref "GATE89") (pin "Q") (pinfunction "Q_Q") (pintype "output"))
      (node (ref "GATE90") (pin "A") (pinfunction "A_A") (pintype "input"))
      (node (ref "GATE92") (pin "B") (pinfunction "B_B") (pintype "input"))
    )
    (net (code "111") (name "Net-(GATE93-PadQ)") (class "Default")
      (node (ref "GATE93") (pin "Q") (pinfunction "Q_Q") (pintype "output"))
      (node (ref "GATE94") (pin "A") (pinfunction "A_A") (pintype "input"))
    )
    (net (code "112") (name "Net-(GATE94-PadB)") (class "Default")
      (node (ref "GATE94") (pin "B") (pinfunction "B_B") (pintype "input"))
      (node (ref "GATE95") (pin "Q") (pinfunction "Q_Q") (pintype "output"))
      (node (ref "GATE96") (pin "A") (pinfunction "A_A") (pintype "input"))
    )
    (net (code "113") (name "Net-(GATE96-PadQ)") (class "Default")
      (node (ref "GATE96") (pin "Q") (pinfunction "Q_Q") (pintype "output"))
      (node (ref "GATE97") (pin "A") (pinfunction "A_A") (pintype "input"))
    )
    (net (code "114") (name "Net-(GATE98-PadQ)") (class "Default")
      (node (ref "GATE98") (pin "Q") (pinfunction "Q_Q") (pintype "output"))
      (node (ref "GATE99") (pin "C") (pinfunction "C_C") (pintype "input"))
    )
    (net (code "115") (name "Net-(GATE100-PadA)") (class "Default")
      (node (ref "GATE100") (pin "A") (pinfunction "A_A") (pintype "input"))
      (node (ref "GATE102") (pin "A") (pinfunction "A_A") (pintype "input"))
      (node (ref "GATE105") (pin "A") (pinfunction "A_A") (pintype "input"))
      (node (ref "GATE108") (pin "A") (pinfunction "A_A") (pintype "input"))
      (node (ref "GATE72") (pin "B") (pinfunction "B_B") (pintype "input"))
      (node (ref "GATE73") (pin "B") (pinfunction "B_B") (pintype "input"))
      (node (ref "GATE74") (pin "Q") (pinfunction "Q_Q") (pintype "output"))
    )
    (net (code "116") (name "Net-(GATE100-PadQ)") (class "Default")
      (node (ref "GATE100") (pin "Q") (pinfunction "Q_Q") (pintype "output"))
      (node (ref "GATE101") (pin "A") (pinfunction "A_A") (pintype "input"))
    )
    (net (code "117") (name "Net-(GATE102-PadC)") (class "Default")
      (node (ref "GATE102") (pin "C") (pinfunction "C_C") (pintype "input"))
      (node (ref "GATE109") (pin "B") (pinfunction "B_B") (pintype "input"))
      (node (ref "GATE84") (pin "B") (pinfunction "B_B") (pintype "input"))
      (node (ref "GATE85") (pin "B") (pinfunction "B_B") (pintype "input"))
      (node (ref "GATE86") (pin "Q") (pinfunction "Q_Q") (pintype "output"))
      (node (ref "GATE93") (pin "B") (pinfunction "B_B") (pintype "input"))
    )
    (net (code "118") (name "Net-(GATE102-PadQ)") (class "Default")
      (node (ref "GATE102") (pin "Q") (pinfunction "Q_Q") (pintype "output"))
      (node (ref "GATE103") (pin "A") (pinfunction "A_A") (pintype "input"))
    )
    (net (code "119") (name "Net-(GATE103-PadB)") (class "Default")
      (node (ref "GATE103") (pin "B") (pinfunction "B_B") (pintype "input"))
      (node (ref "GATE104") (pin "Q") (pinfunction "Q_Q") (pintype "output"))
    )
    (net (code "120") (name "Net-(GATE103-PadC)") (class "Default")
      (node (ref "GATE103") (pin "C") (pinfunction "C_C") (pintype "input"))
      (node (ref "GATE105") (pin "Q") (pinfunction "Q_Q") (pintype "output"))
    )
    (net (code "121") (name "Net-(GATE104-PadC)") (class "Default")
      (node (ref "GATE104") (pin "C") (pinfunction "C_C") (pintype "input"))
      (node (ref "GATE108") (pin "C") (pinfunction "C_C") (pintype "input"))
      (node (ref "GATE90") (pin "B") (pinfunction "B_B") (pintype "input"))
      (node (ref "GATE91") (pin "B") (pinfunction "B_B") (pintype "input"))
      (node (ref "GATE92") (pin "Q") (pinfunction "Q_Q") (pintype "output"))
      (node (ref "GATE93") (pin "A") (pinfunction "A_A") (pintype "input"))
    )
    (net (code "122") (name "Net-(GATE105-PadB)") (class "Default")
      (node (ref "GATE105") (pin "B") (pinfunction "B_B") (pintype "input"))
      (node (ref "GATE109") (pin "A") (pinfunction "A_A") (pintype "input"))
      (node (ref "GATE78") (pin "B") (pinfunction "B_B") (pintype "input"))
      (node (ref "GATE79") (pin "B") (pinfunction "B_B") (pintype "input"))
      (node (ref "GATE80") (pin "Q") (pinfunction "Q_Q") (pintype "output"))
    )
    (net (code "123") (name "Net-(GATE106-PadQ)") (class "Default")
      (node (ref "GATE106") (pin "Q") (pinfunction "Q_Q") (pintype "output"))
      (node (ref "GATE107") (pin "A") (pinfunction "A_A") (pintype "input"))
    )
    (net (code "124") (name "Net-(GATE107-PadB)") (class "Default")
      (node (ref "GATE107") (pin "B") (pinfunction "B_B") (pintype "input"))
      (node (ref "GATE108") (pin "Q") (pinfunction "Q_Q") (pintype "output"))
    )
    (net (code "125") (name "Net-(GATE107-PadC)") (class "Default")
      (node (ref "GATE107") (pin "C") (pinfunction "C_C") (pintype "input"))
      (node (ref "GATE109") (pin "Q") (pinfunction "Q_Q") (pintype "output"))
    )
    (net (code "126") (name "Net-(GATE110-PadB)") (class "Default")
      (node (ref "GATE110") (pin "B") (pinfunction "B_B") (pintype "input"))
      (node (ref "GATE112") (pin "C") (pinfunction "C_C") (pintype "input"))
      (node (ref "GATE113") (pin "Q") (pinfunction "Q_Q") (pintype "output"))
    )
    (net (code "127") (name "Net-(GATE110-PadC)") (class "Default")
      (node (ref "GATE110") (pin "C") (pinfunction "C_C") (pintype "input"))
      (node (ref "GATE111") (pin "Q") (pinfunction "Q_Q") (pintype "output"))
      (node (ref "GATE112") (pin "A") (pinfunction "A_A") (pintype "input"))
      (node (ref "GATE114") (pin "A") (pinfunction "A_A") (pintype "input"))
    )
    (net (code "128") (name "Net-(GATE110-PadQ)") (class "Default")
      (node (ref "GATE110") (pin "Q") (pinfunction "Q_Q") (pintype "output"))
      (node (ref "GATE111") (pin "A") (pinfunction "A_A") (pintype "input"))
    )
    (net (code "129") (name "Net-(GATE111-PadB)") (class "Default")
      (node (ref "GATE111") (pin "B") (pinfunction "B_B") (pintype "input"))
      (node (ref "GATE112") (pin "B") (pinfunction "B_B") (pintype "input"))
      (node (ref "GATE134") (pin "Q") (pinfunction "Q_Q") (pintype "output"))
    )
    (net (code "130") (name "Net-(GATE112-PadQ)") (class "Default")
      (node (ref "GATE112") (pin "Q") (pinfunction "Q_Q") (pintype "output"))
      (node (ref "GATE113") (pin "A") (pinfunction "A_A") (pintype "input"))
      (node (ref "GATE115") (pin "B") (pinfunction "B_B") (pintype "input"))
    )
    (net (code "131") (name "Net-(GATE113-PadB)") (class "Default")
      (node (ref "GATE113") (pin "B") (pinfunction "B_B") (pintype "input"))
      (node (ref "GATE114") (pin "B") (pinfunction "B_B") (pintype "input"))
      (node (ref "GATE115") (pin "Q") (pinfunction "Q_Q") (pintype "output"))
      (node (ref "GATE128") (pin "C") (pinfunction "C_C") (pintype "input"))
    )
    (net (code "132") (name "Net-(GATE116-PadB)") (class "Default")
      (node (ref "GATE116") (pin "B") (pinfunction "B_B") (pintype "input"))
      (node (ref "GATE118") (pin "C") (pinfunction "C_C") (pintype "input"))
      (node (ref "GATE119") (pin "Q") (pinfunction "Q_Q") (pintype "output"))
    )
    (net (code "133") (name "Net-(GATE116-PadC)") (class "Default")
      (node (ref "GATE116") (pin "C") (pinfunction "C_C") (pintype "input"))
      (node (ref "GATE117") (pin "Q") (pinfunction "Q_Q") (pintype "output"))
      (node (ref "GATE118") (pin "A") (pinfunction "A_A") (pintype "input"))
      (node (ref "GATE120") (pin "A") (pinfunction "A_A") (pintype "input"))
    )
    (net (code "134") (name "Net-(GATE116-PadQ)") (class "Default")
      (node (ref "GATE116") (pin "Q") (pinfunction "Q_Q") (pintype "output"))
      (node (ref "GATE117") (pin "A") (pinfunction "A_A") (pintype "input"))
    )
    (net (code "135") (name "Net-(GATE118-PadQ)") (class "Default")
      (node (ref "GATE118") (pin "Q") (pinfunction "Q_Q") (pintype "output"))
      (node (ref "GATE119") (pin "A") (pinfunction "A_A") (pintype "input"))
      (node (ref "GATE121") (pin "B") (pinfunction "B_B") (pintype "input"))
    )
    (net (code "136") (name "Net-(GATE119-PadB)") (class "Default")
      (node (ref "GATE119") (pin "B") (pinfunction "B_B") (pintype "input"))
      (node (ref "GATE120") (pin "B") (pinfunction "B_B") (pintype "input"))
      (node (ref "GATE121") (pin "Q") (pinfunction "Q_Q") (pintype "output"))
      (node (ref "GATE128") (pin "B") (pinfunction "B_B") (pintype "input"))
    )
    (net (code "137") (name "Net-(GATE122-PadB)") (class "Default")
      (node (ref "GATE122") (pin "B") (pinfunction "B_B") (pintype "input"))
      (node (ref "GATE124") (pin "C") (pinfunction "C_C") (pintype "input"))
      (node (ref "GATE125") (pin "Q") (pinfunction "Q_Q") (pintype "output"))
    )
    (net (code "138") (name "Net-(GATE122-PadC)") (class "Default")
      (node (ref "GATE122") (pin "C") (pinfunction "C_C") (pintype "input"))
      (node (ref "GATE123") (pin "Q") (pinfunction "Q_Q") (pintype "output"))
      (node (ref "GATE124") (pin "A") (pinfunction "A_A") (pintype "input"))
      (node (ref "GATE126") (pin "A") (pinfunction "A_A") (pintype "input"))
    )
    (net (code "139") (name "Net-(GATE122-PadQ)") (class "Default")
      (node (ref "GATE122") (pin "Q") (pinfunction "Q_Q") (pintype "output"))
      (node (ref "GATE123") (pin "A") (pinfunction "A_A") (pintype "input"))
    )
    (net (code "140") (name "Net-(GATE124-PadQ)") (class "Default")
      (node (ref "GATE124") (pin "Q") (pinfunction "Q_Q") (pintype "output"))
      (node (ref "GATE125") (pin "A") (pinfunction "A_A") (pintype "input"))
      (node (ref "GATE127") (pin "B") (pinfunction "B_B") (pintype "input"))
    )
    (net (code "141") (name "Net-(GATE125-PadB)") (class "Default")
      (node (ref "GATE125") (pin "B") (pinfunction "B_B") (pintype "input"))
      (node (ref "GATE126") (pin "B") (pinfunction "B_B") (pintype "input"))
      (node (ref "GATE127") (pin "Q") (pinfunction "Q_Q") (pintype "output"))
      (node (ref "GATE128") (pin "A") (pinfunction "A_A") (pintype "input"))
    )
    (net (code "142") (name "Net-(GATE128-PadQ)") (class "Default")
      (node (ref "GATE128") (pin "Q") (pinfunction "Q_Q") (pintype "output"))
      (node (ref "GATE129") (pin "A") (pinfunction "A_A") (pintype "input"))
    )
    (net (code "143") (name "Net-(GATE129-PadB)") (class "Default")
      (node (ref "GATE129") (pin "B") (pinfunction "B_B") (pintype "input"))
      (node (ref "GATE130") (pin "Q") (pinfunction "Q_Q") (pintype "output"))
      (node (ref "GATE131") (pin "A") (pinfunction "A_A") (pintype "input"))
    )
    (net (code "144") (name "Net-(GATE129-PadQ)") (class "Default")
      (node (ref "GATE129") (pin "Q") (pinfunction "Q_Q") (pintype "output"))
      (node (ref "GATE130") (pin "A") (pinfunction "A_A") (pintype "input"))
    )
    (net (code "145") (name "Net-(GATE131-PadQ)") (class "Default")
      (node (ref "GATE131") (pin "Q") (pinfunction "Q_Q") (pintype "output"))
      (node (ref "GATE132") (pin "A") (pinfunction "A_A") (pintype "input"))
    )
    (net (code "146") (name "Net-(GATE133-PadQ)") (class "Default")
      (node (ref "GATE133") (pin "Q") (pinfunction "Q_Q") (pintype "output"))
      (node (ref "GATE134") (pin "C") (pinfunction "C_C") (pintype "input"))
    )
    (net (code "147") (name "Net-(GATE135-PadA)") (class "Default")
      (node (ref "GATE135") (pin "A") (pinfunction "A_A") (pintype "input"))
      (node (ref "GATE142") (pin "Q") (pinfunction "Q_Q") (pintype "output"))
    )
    (net (code "148") (name "Net-(GATE135-PadB)") (class "Default")
      (node (ref "GATE135") (pin "B") (pinfunction "B_B") (pintype "input"))
      (node (ref "GATE137") (pin "C") (pinfunction "C_C") (pintype "input"))
      (node (ref "GATE138") (pin "Q") (pinfunction "Q_Q") (pintype "output"))
    )
    (net (code "149") (name "Net-(GATE135-PadC)") (class "Default")
      (node (ref "GATE135") (pin "C") (pinfunction "C_C") (pintype "input"))
      (node (ref "GATE136") (pin "Q") (pinfunction "Q_Q") (pintype "output"))
      (node (ref "GATE137") (pin "A") (pinfunction "A_A") (pintype "input"))
      (node (ref "GATE139") (pin "A") (pinfunction "A_A") (pintype "input"))
    )
    (net (code "150") (name "Net-(GATE135-PadQ)") (class "Default")
      (node (ref "GATE135") (pin "Q") (pinfunction "Q_Q") (pintype "output"))
      (node (ref "GATE136") (pin "A") (pinfunction "A_A") (pintype "input"))
    )
    (net (code "151") (name "Net-(GATE137-PadQ)") (class "Default")
      (node (ref "GATE137") (pin "Q") (pinfunction "Q_Q") (pintype "output"))
      (node (ref "GATE138") (pin "A") (pinfunction "A_A") (pintype "input"))
      (node (ref "GATE140") (pin "B") (pinfunction "B_B") (pintype "input"))
    )
    (net (code "152") (name "Net-(GATE141-PadQ)") (class "Default")
      (node (ref "GATE141") (pin "Q") (pinfunction "Q_Q") (pintype "output"))
      (node (ref "GATE142") (pin "A") (pinfunction "A_A") (pintype "input"))
    )
    (net (code "153") (name "Net-(GATE143-PadQ)") (class "Default")
      (node (ref "GATE143") (pin "Q") (pinfunction "Q_Q") (pintype "output"))
      (node (ref "GATE30") (pin "A") (pinfunction "A_A") (pintype "input"))
    )
    (net (code "154") (name "Net-(GATE144-PadA)") (class "Default")
      (node (ref "GATE144") (pin "A") (pinfunction "A_A") (pintype "input"))
      (node (ref "GATE68") (pin "Q") (pinfunction "Q_Q") (pintype "output"))
    )
    (net (code "155") (name "Net-(GATE144-PadQ)") (class "Default")
      (node (ref "GATE144") (pin "Q") (pinfunction "Q_Q") (pintype "output"))
      (node (ref "GATE145") (pin "A") (pinfunction "A_A") (pintype "input"))
    )
    (net (code "156") (name "Net-(GATE146-PadQ)") (class "Default")
      (node (ref "GATE146") (pin "Q") (pinfunction "Q_Q") (pintype "output"))
      (node (ref "GATE147") (pin "B") (pinfunction "B_B") (pintype "input"))
    )
    (net (code "157") (name "Net-(GATE147-PadQ)") (class "Default")
      (node (ref "GATE147") (pin "Q") (pinfunction "Q_Q") (pintype "output"))
      (node (ref "GATE149") (pin "B") (pinfunction "B_B") (pintype "input"))
    )
    (net (code "158") (name "Net-(GATE148-PadA)") (class "Default")
      (node (ref "GATE148") (pin "A") (pinfunction "A_A") (pintype "input"))
      (node (ref "GATE30") (pin "Q") (pinfunction "Q_Q") (pintype "output"))
    )
    (net (code "159") (name "Net-(GATE148-PadQ)") (class "Default")
      (node (ref "GATE148") (pin "Q") (pinfunction "Q_Q") (pintype "output"))
      (node (ref "GATE149") (pin "A") (pinfunction "A_A") (pintype "input"))
    )
    (net (code "160") (name "Net-(Q1-G)") (class "Default")
      (node (ref "C3\\") (pin "2") (pinfunction "2_2") (pintype "passive"))
      (node (ref "Q1") (pin "2") (pinfunction "G_2") (pintype "passive"))
      (node (ref "R2") (pin "2") (pinfunction "2_2") (pintype "passive"))
    )
    (net (code "161") (name "Net-(Q2-G)") (class "Default")
      (node (ref "C4") (pin "2") (pinfunction "2_2") (pintype "passive"))
      (node (ref "Q2") (pin "2") (pinfunction "G_2") (pintype "passive"))
      (node (ref "R5") (pin "2") (pinfunction "2_2") (pintype "passive"))
    )
    (net (code "162") (name "Net-(Q3-G)") (class "Default")
      (node (ref "C5") (pin "2") (pinfunction "2_2") (pintype "passive"))
      (node (ref "Q3") (pin "2") (pinfunction "G_2") (pintype "passive"))
      (node (ref "R8") (pin "2") (pinfunction "2_2") (pintype "passive"))
    )
    (net (code "163") (name "Net-(Q4-G)") (class "Default")
      (node (ref "C6") (pin "2") (pinfunction "2_2") (pintype "passive"))
      (node (ref "Q4") (pin "2") (pinfunction "G_2") (pintype "passive"))
      (node (ref "R11") (pin "2") (pinfunction "2_2") (pintype "passive"))
    )
    (net (code "164") (name "Net-(R1-Pad2)") (class "Default")
      (node (ref "R1") (pin "2") (pinfunction "2_2") (pintype "passive"))
      (node (ref "R2") (pin "1") (pinfunction "1_1") (pintype "passive"))
      (node (ref "SW1") (pin "1") (pinfunction "1_1") (pintype "passive"))
      (node (ref "SW1") (pin "2") (pinfunction "2_2") (pintype "passive"))
    )
    (net (code "165") (name "Net-(R4-Pad2)") (class "Default")
      (node (ref "R4") (pin "2") (pinfunction "2_2") (pintype "passive"))
      (node (ref "R5") (pin "1") (pinfunction "1_1") (pintype "passive"))
      (node (ref "SW2") (pin "1") (pinfunction "1_1") (pintype "passive"))
      (node (ref "SW2") (pin "2") (pinfunction "2_2") (pintype "passive"))
    )
    (net (code "166") (name "Net-(R7-Pad2)") (class "Default")
      (node (ref "R7") (pin "2") (pinfunction "2_2") (pintype "passive"))
      (node (ref "R8") (pin "1") (pinfunction "1_1") (pintype "passive"))
      (node (ref "SW3") (pin "1") (pinfunction "1_1") (pintype "passive"))
      (node (ref "SW3") (pin "2") (pinfunction "2_2") (pintype "passive"))
    )
    (net (code "167") (name "Net-(R10-Pad2)") (class "Default")
      (node (ref "R10") (pin "2") (pinfunction "2_2") (pintype "passive"))
      (node (ref "R11") (pin "1") (pinfunction "1_1") (pintype "passive"))
      (node (ref "SW4") (pin "1") (pinfunction "1_1") (pintype "passive"))
      (node (ref "SW4") (pin "2") (pinfunction "2_2") (pintype "passive"))
    )
    (net (code "168") (name "VDD") (class "Default")
      (node (ref "A_BUS") (pin "38") (pinfunction "38_38") (pintype "passive"))
      (node (ref "A_BUS") (pin "40") (pinfunction "40_40") (pintype "passive"))
      (node (ref "C1") (pin "+") (pinfunction "+_+") (pintype "passive"))
      (node (ref "R1") (pin "1") (pinfunction "1_1") (pintype "passive"))
      (node (ref "R10") (pin "1") (pinfunction "1_1") (pintype "passive"))
      (node (ref "R12") (pin "2") (pinfunction "2_2") (pintype "passive"))
      (node (ref "R3") (pin "2") (pinfunction "2_2") (pintype "passive"))
      (node (ref "R4") (pin "1") (pinfunction "1_1") (pintype "passive"))
      (node (ref "R6") (pin "2") (pinfunction "2_2") (pintype "passive"))
      (node (ref "R7") (pin "1") (pinfunction "1_1") (pintype "passive"))
      (node (ref "R9") (pin "2") (pinfunction "2_2") (pintype "passive"))
    )
    (net (code "169") (name "VSS") (class "Default")
      (node (ref "A_BUS") (pin "37") (pinfunction "37_37") (pintype "passive"))
      (node (ref "A_BUS") (pin "39") (pinfunction "39_39") (pintype "passive"))
      (node (ref "C1") (pin "-") (pinfunction "-_-") (pintype "passive"))
      (node (ref "C2") (pin "2") (pinfunction "2_2") (pintype "passive"))
      (node (ref "C3") (pin "2") (pinfunction "2_2") (pintype "passive"))
      (node (ref "C3\\") (pin "1") (pinfunction "1_1") (pintype "passive"))
      (node (ref "C4") (pin "1") (pinfunction "1_1") (pintype "passive"))
      (node (ref "C5") (pin "1") (pinfunction "1_1") (pintype "passive"))
      (node (ref "C6") (pin "1") (pinfunction "1_1") (pintype "passive"))
      (node (ref "Q1") (pin "1") (pinfunction "S_1") (pintype "passive"))
      (node (ref "Q2") (pin "1") (pinfunction "S_1") (pintype "passive"))
      (node (ref "Q3") (pin "1") (pinfunction "S_1") (pintype "passive"))
      (node (ref "Q4") (pin "1") (pinfunction "S_1") (pintype "passive"))
      (node (ref "SW1") (pin "3") (pinfunction "3_3") (pintype "passive"))
      (node (ref "SW1") (pin "4") (pinfunction "4_4") (pintype "passive"))
      (node (ref "SW2") (pin "3") (pinfunction "3_3") (pintype "passive"))
      (node (ref "SW2") (pin "4") (pinfunction "4_4") (pintype "passive"))
      (node (ref "SW3") (pin "3") (pinfunction "3_3") (pintype "passive"))
      (node (ref "SW3") (pin "4") (pinfunction "4_4") (pintype "passive"))
      (node (ref "SW4") (pin "3") (pinfunction "3_3") (pintype "passive"))
      (node (ref "SW4") (pin "4") (pinfunction "4_4") (pintype "passive"))
    )
    (net (code "170") (name "unconnected-(A_BUS-Pad1)") (class "Default")
      (node (ref "A_BUS") (pin "1") (pinfunction "1_1") (pintype "passive"))
    )
    (net (code "171") (name "unconnected-(A_BUS-Pad2)") (class "Default")
      (node (ref "A_BUS") (pin "2") (pinfunction "2_2") (pintype "passive"))
    )
    (net (code "172") (name "unconnected-(A_BUS-Pad3)") (class "Default")
      (node (ref "A_BUS") (pin "3") (pinfunction "3_3") (pintype "passive"))
    )
    (net (code "173") (name "unconnected-(A_BUS-Pad4)") (class "Default")
      (node (ref "A_BUS") (pin "4") (pinfunction "4_4") (pintype "passive"))
    )
    (net (code "174") (name "unconnected-(A_BUS-Pad5)") (class "Default")
      (node (ref "A_BUS") (pin "5") (pinfunction "5_5") (pintype "passive"))
    )
    (net (code "175") (name "unconnected-(A_BUS-Pad6)") (class "Default")
      (node (ref "A_BUS") (pin "6") (pinfunction "6_6") (pintype "passive"))
    )
    (net (code "176") (name "unconnected-(A_BUS-Pad7)") (class "Default")
      (node (ref "A_BUS") (pin "7") (pinfunction "7_7") (pintype "passive"))
    )
    (net (code "177") (name "unconnected-(A_BUS-Pad8)") (class "Default")
      (node (ref "A_BUS") (pin "8") (pinfunction "8_8") (pintype "passive"))
    )
    (net (code "178") (name "unconnected-(A_BUS-Pad9)") (class "Default")
      (node (ref "A_BUS") (pin "9") (pinfunction "9_9") (pintype "passive"))
    )
    (net (code "179") (name "unconnected-(A_BUS-Pad10)") (class "Default")
      (node (ref "A_BUS") (pin "10") (pinfunction "10_10") (pintype "passive"))
    )
    (net (code "180") (name "unconnected-(A_BUS-Pad11)") (class "Default")
      (node (ref "A_BUS") (pin "11") (pinfunction "11_11") (pintype "passive"))
    )
    (net (code "181") (name "unconnected-(A_BUS-Pad12)") (class "Default")
      (node (ref "A_BUS") (pin "12") (pinfunction "12_12") (pintype "passive"))
    )
    (net (code "182") (name "unconnected-(A_BUS-Pad13)") (class "Default")
      (node (ref "A_BUS") (pin "13") (pinfunction "13_13") (pintype "passive"))
    )
    (net (code "183") (name "unconnected-(A_BUS-Pad14)") (class "Default")
      (node (ref "A_BUS") (pin "14") (pinfunction "14_14") (pintype "passive"))
    )
    (net (code "184") (name "unconnected-(A_BUS-Pad15)") (class "Default")
      (node (ref "A_BUS") (pin "15") (pinfunction "15_15") (pintype "passive"))
    )
    (net (code "185") (name "unconnected-(A_BUS-Pad16)") (class "Default")
      (node (ref "A_BUS") (pin "16") (pinfunction "16_16") (pintype "passive"))
    )
    (net (code "186") (name "unconnected-(A_BUS-Pad17)") (class "Default")
      (node (ref "A_BUS") (pin "17") (pinfunction "17_17") (pintype "passive"))
    )
    (net (code "187") (name "unconnected-(A_BUS-Pad18)") (class "Default")
      (node (ref "A_BUS") (pin "18") (pinfunction "18_18") (pintype "passive"))
    )
    (net (code "188") (name "unconnected-(A_BUS-Pad19)") (class "Default")
      (node (ref "A_BUS") (pin "19") (pinfunction "19_19") (pintype "passive"))
    )
    (net (code "189") (name "unconnected-(A_BUS-Pad20)") (class "Default")
      (node (ref "A_BUS") (pin "20") (pinfunction "20_20") (pintype "passive"))
    )
    (net (code "190") (name "unconnected-(A_BUS-Pad21)") (class "Default")
      (node (ref "A_BUS") (pin "21") (pinfunction "21_21") (pintype "passive"))
    )
    (net (code "191") (name "unconnected-(A_BUS-Pad22)") (class "Default")
      (node (ref "A_BUS") (pin "22") (pinfunction "22_22") (pintype "passive"))
    )
    (net (code "192") (name "unconnected-(A_BUS-Pad23)") (class "Default")
      (node (ref "A_BUS") (pin "23") (pinfunction "23_23") (pintype "passive"))
    )
    (net (code "193") (name "unconnected-(A_BUS-Pad24)") (class "Default")
      (node (ref "A_BUS") (pin "24") (pinfunction "24_24") (pintype "passive"))
    )
    (net (code "194") (name "unconnected-(A_BUS-Pad25)") (class "Default")
      (node (ref "A_BUS") (pin "25") (pinfunction "25_25") (pintype "passive"))
    )
    (net (code "195") (name "unconnected-(A_BUS-Pad26)") (class "Default")
      (node (ref "A_BUS") (pin "26") (pinfunction "26_26") (pintype "passive"))
    )
    (net (code "196") (name "unconnected-(A_BUS-Pad36)") (class "Default")
      (node (ref "A_BUS") (pin "36") (pinfunction "36_36") (pintype "passive"))
    )
    (net (code "197") (name "unconnected-(B_BUS-Pad14)") (class "Default")
      (node (ref "B_BUS") (pin "14") (pinfunction "14_14") (pintype "passive"))
    )
    (net (code "198") (name "unconnected-(B_BUS-Pad15)") (class "Default")
      (node (ref "B_BUS") (pin "15") (pinfunction "15_15") (pintype "passive"))
    )
    (net (code "199") (name "unconnected-(B_BUS-Pad16)") (class "Default")
      (node (ref "B_BUS") (pin "16") (pinfunction "16_16") (pintype "passive"))
    )
    (net (code "200") (name "unconnected-(B_BUS-Pad17)") (class "Default")
      (node (ref "B_BUS") (pin "17") (pinfunction "17_17") (pintype "passive"))
    )
    (net (code "201") (name "unconnected-(B_BUS-Pad18)") (class "Default")
      (node (ref "B_BUS") (pin "18") (pinfunction "18_18") (pintype "passive"))
    )
    (net (code "202") (name "unconnected-(B_BUS-Pad19)") (class "Default")
      (node (ref "B_BUS") (pin "19") (pinfunction "19_19") (pintype "passive"))
    )
    (net (code "203") (name "unconnected-(B_BUS-Pad20)") (class "Default")
      (node (ref "B_BUS") (pin "20") (pinfunction "20_20") (pintype "passive"))
    )
    (net (code "204") (name "unconnected-(B_BUS-Pad21)") (class "Default")
      (node (ref "B_BUS") (pin "21") (pinfunction "21_21") (pintype "passive"))
    )
    (net (code "205") (name "unconnected-(B_BUS-Pad22)") (class "Default")
      (node (ref "B_BUS") (pin "22") (pinfunction "22_22") (pintype "passive"))
    )
    (net (code "206") (name "unconnected-(B_BUS-Pad23)") (class "Default")
      (node (ref "B_BUS") (pin "23") (pinfunction "23_23") (pintype "passive"))
    )
    (net (code "207") (name "unconnected-(B_BUS-Pad24)") (class "Default")
      (node (ref "B_BUS") (pin "24") (pinfunction "24_24") (pintype "passive"))
    )
    (net (code "208") (name "unconnected-(B_BUS-Pad25)") (class "Default")
      (node (ref "B_BUS") (pin "25") (pinfunction "25_25") (pintype "passive"))
    )
    (net (code "209") (name "unconnected-(B_BUS-Pad26)") (class "Default")
      (node (ref "B_BUS") (pin "26") (pinfunction "26_26") (pintype "passive"))
    )
    (net (code "210") (name "unconnected-(B_BUS-Pad27)") (class "Default")
      (node (ref "B_BUS") (pin "27") (pinfunction "27_27") (pintype "passive"))
    )
    (net (code "211") (name "unconnected-(B_BUS-Pad28)") (class "Default")
      (node (ref "B_BUS") (pin "28") (pinfunction "28_28") (pintype "passive"))
    )
    (net (code "212") (name "unconnected-(B_BUS-Pad29)") (class "Default")
      (node (ref "B_BUS") (pin "29") (pinfunction "29_29") (pintype "passive"))
    )
    (net (code "213") (name "unconnected-(B_BUS-Pad30)") (class "Default")
      (node (ref "B_BUS") (pin "30") (pinfunction "30_30") (pintype "passive"))
    )
    (net (code "214") (name "unconnected-(B_BUS-Pad31)") (class "Default")
      (node (ref "B_BUS") (pin "31") (pinfunction "31_31") (pintype "passive"))
    )
    (net (code "215") (name "unconnected-(B_BUS-Pad32)") (class "Default")
      (node (ref "B_BUS") (pin "32") (pinfunction "32_32") (pintype "passive"))
    )
    (net (code "216") (name "unconnected-(B_BUS-Pad33)") (class "Default")
      (node (ref "B_BUS") (pin "33") (pinfunction "33_33") (pintype "passive"))
    )
    (net (code "217") (name "unconnected-(B_BUS-Pad34)") (class "Default")
      (node (ref "B_BUS") (pin "34") (pinfunction "34_34") (pintype "passive"))
    )
    (net (code "218") (name "unconnected-(B_BUS-Pad35)") (class "Default")
      (node (ref "B_BUS") (pin "35") (pinfunction "35_35") (pintype "passive"))
    )
    (net (code "219") (name "unconnected-(B_BUS-Pad36)") (class "Default")
      (node (ref "B_BUS") (pin "36") (pinfunction "36_36") (pintype "passive"))
    )
    (net (code "220") (name "unconnected-(B_BUS-Pad37)") (class "Default")
      (node (ref "B_BUS") (pin "37") (pinfunction "37_37") (pintype "passive"))
    )
    (net (code "221") (name "unconnected-(B_BUS-Pad38)") (class "Default")
      (node (ref "B_BUS") (pin "38") (pinfunction "38_38") (pintype "passive"))
    )
    (net (code "222") (name "unconnected-(B_BUS-Pad39)") (class "Default")
      (node (ref "B_BUS") (pin "39") (pinfunction "39_39") (pintype "passive"))
    )
    (net (code "223") (name "unconnected-(B_BUS-Pad40)") (class "Default")
      (node (ref "B_BUS") (pin "40") (pinfunction "40_40") (pintype "passive"))
    )
    (net (code "224") (name "unconnected-(C_BUS-Pad1)") (class "Default")
      (node (ref "C_BUS") (pin "1") (pinfunction "1_1") (pintype "passive"))
    )
    (net (code "225") (name "unconnected-(C_BUS-Pad2)") (class "Default")
      (node (ref "C_BUS") (pin "2") (pinfunction "2_2") (pintype "passive"))
    )
    (net (code "226") (name "unconnected-(C_BUS-Pad3)") (class "Default")
      (node (ref "C_BUS") (pin "3") (pinfunction "3_3") (pintype "passive"))
    )
    (net (code "227") (name "unconnected-(C_BUS-Pad4)") (class "Default")
      (node (ref "C_BUS") (pin "4") (pinfunction "4_4") (pintype "passive"))
    )
    (net (code "228") (name "unconnected-(C_BUS-Pad5)") (class "Default")
      (node (ref "C_BUS") (pin "5") (pinfunction "5_5") (pintype "passive"))
    )
    (net (code "229") (name "unconnected-(C_BUS-Pad6)") (class "Default")
      (node (ref "C_BUS") (pin "6") (pinfunction "6_6") (pintype "passive"))
    )
    (net (code "230") (name "unconnected-(C_BUS-Pad7)") (class "Default")
      (node (ref "C_BUS") (pin "7") (pinfunction "7_7") (pintype "passive"))
    )
    (net (code "231") (name "unconnected-(C_BUS-Pad8)") (class "Default")
      (node (ref "C_BUS") (pin "8") (pinfunction "8_8") (pintype "passive"))
    )
    (net (code "232") (name "unconnected-(C_BUS-Pad9)") (class "Default")
      (node (ref "C_BUS") (pin "9") (pinfunction "9_9") (pintype "passive"))
    )
    (net (code "233") (name "unconnected-(C_BUS-Pad10)") (class "Default")
      (node (ref "C_BUS") (pin "10") (pinfunction "10_10") (pintype "passive"))
    )
    (net (code "234") (name "unconnected-(C_BUS-Pad11)") (class "Default")
      (node (ref "C_BUS") (pin "11") (pinfunction "11_11") (pintype "passive"))
    )
    (net (code "235") (name "unconnected-(C_BUS-Pad12)") (class "Default")
      (node (ref "C_BUS") (pin "12") (pinfunction "12_12") (pintype "passive"))
    )
    (net (code "236") (name "unconnected-(C_BUS-Pad13)") (class "Default")
      (node (ref "C_BUS") (pin "13") (pinfunction "13_13") (pintype "passive"))
    )
    (net (code "237") (name "unconnected-(C_BUS-Pad14)") (class "Default")
      (node (ref "C_BUS") (pin "14") (pinfunction "14_14") (pintype "passive"))
    )
    (net (code "238") (name "unconnected-(C_BUS-Pad15)") (class "Default")
      (node (ref "C_BUS") (pin "15") (pinfunction "15_15") (pintype "passive"))
    )
    (net (code "239") (name "unconnected-(C_BUS-Pad16)") (class "Default")
      (node (ref "C_BUS") (pin "16") (pinfunction "16_16") (pintype "passive"))
    )
    (net (code "240") (name "unconnected-(C_BUS-Pad17)") (class "Default")
      (node (ref "C_BUS") (pin "17") (pinfunction "17_17") (pintype "passive"))
    )
    (net (code "241") (name "unconnected-(C_BUS-Pad18)") (class "Default")
      (node (ref "C_BUS") (pin "18") (pinfunction "18_18") (pintype "passive"))
    )
    (net (code "242") (name "unconnected-(C_BUS-Pad19)") (class "Default")
      (node (ref "C_BUS") (pin "19") (pinfunction "19_19") (pintype "passive"))
    )
    (net (code "243") (name "unconnected-(C_BUS-Pad20)") (class "Default")
      (node (ref "C_BUS") (pin "20") (pinfunction "20_20") (pintype "passive"))
    )
    (net (code "244") (name "unconnected-(C_BUS-Pad21)") (class "Default")
      (node (ref "C_BUS") (pin "21") (pinfunction "21_21") (pintype "passive"))
    )
    (net (code "245") (name "unconnected-(C_BUS-Pad22)") (class "Default")
      (node (ref "C_BUS") (pin "22") (pinfunction "22_22") (pintype "passive"))
    )
    (net (code "246") (name "unconnected-(C_BUS-Pad23)") (class "Default")
      (node (ref "C_BUS") (pin "23") (pinfunction "23_23") (pintype "passive"))
    )
    (net (code "247") (name "unconnected-(C_BUS-Pad24)") (class "Default")
      (node (ref "C_BUS") (pin "24") (pinfunction "24_24") (pintype "passive"))
    )
    (net (code "248") (name "unconnected-(C_BUS-Pad25)") (class "Default")
      (node (ref "C_BUS") (pin "25") (pinfunction "25_25") (pintype "passive"))
    )
    (net (code "249") (name "unconnected-(C_BUS-Pad26)") (class "Default")
      (node (ref "C_BUS") (pin "26") (pinfunction "26_26") (pintype "passive"))
    )
    (net (code "250") (name "unconnected-(C_BUS-Pad27)") (class "Default")
      (node (ref "C_BUS") (pin "27") (pinfunction "27_27") (pintype "passive"))
    )
    (net (code "251") (name "unconnected-(C_BUS-Pad28)") (class "Default")
      (node (ref "C_BUS") (pin "28") (pinfunction "28_28") (pintype "passive"))
    )
    (net (code "252") (name "unconnected-(C_BUS-Pad29)") (class "Default")
      (node (ref "C_BUS") (pin "29") (pinfunction "29_29") (pintype "passive"))
    )
    (net (code "253") (name "unconnected-(C_BUS-Pad30)") (class "Default")
      (node (ref "C_BUS") (pin "30") (pinfunction "30_30") (pintype "passive"))
    )
    (net (code "254") (name "unconnected-(C_BUS-Pad31)") (class "Default")
      (node (ref "C_BUS") (pin "31") (pinfunction "31_31") (pintype "passive"))
    )
    (net (code "255") (name "unconnected-(C_BUS-Pad32)") (class "Default")
      (node (ref "C_BUS") (pin "32") (pinfunction "32_32") (pintype "passive"))
    )
    (net (code "256") (name "unconnected-(C_BUS-Pad33)") (class "Default")
      (node (ref "C_BUS") (pin "33") (pinfunction "33_33") (pintype "passive"))
    )
    (net (code "257") (name "unconnected-(C_BUS-Pad34)") (class "Default")
      (node (ref "C_BUS") (pin "34") (pinfunction "34_34") (pintype "passive"))
    )
    (net (code "258") (name "unconnected-(C_BUS-Pad35)") (class "Default")
      (node (ref "C_BUS") (pin "35") (pinfunction "35_35") (pintype "passive"))
    )
    (net (code "259") (name "unconnected-(C_BUS-Pad36)") (class "Default")
      (node (ref "C_BUS") (pin "36") (pinfunction "36_36") (pintype "passive"))
    )
    (net (code "260") (name "unconnected-(C_BUS-Pad37)") (class "Default")
      (node (ref "C_BUS") (pin "37") (pinfunction "37_37") (pintype "passive"))
    )
    (net (code "261") (name "unconnected-(C_BUS-Pad38)") (class "Default")
      (node (ref "C_BUS") (pin "38") (pinfunction "38_38") (pintype "passive"))
    )
    (net (code "262") (name "unconnected-(C_BUS-Pad39)") (class "Default")
      (node (ref "C_BUS") (pin "39") (pinfunction "39_39") (pintype "passive"))
    )
    (net (code "263") (name "unconnected-(C_BUS-Pad40)") (class "Default")
      (node (ref "C_BUS") (pin "40") (pinfunction "40_40") (pintype "passive"))
    )
    (net (code "264") (name "unconnected-(D_BUS-Pad1)") (class "Default")
      (node (ref "D_BUS") (pin "1") (pinfunction "1_1") (pintype "passive"))
    )
    (net (code "265") (name "unconnected-(D_BUS-Pad2)") (class "Default")
      (node (ref "D_BUS") (pin "2") (pinfunction "2_2") (pintype "passive"))
    )
    (net (code "266") (name "unconnected-(D_BUS-Pad3)") (class "Default")
      (node (ref "D_BUS") (pin "3") (pinfunction "3_3") (pintype "passive"))
    )
    (net (code "267") (name "unconnected-(D_BUS-Pad4)") (class "Default")
      (node (ref "D_BUS") (pin "4") (pinfunction "4_4") (pintype "passive"))
    )
    (net (code "268") (name "unconnected-(D_BUS-Pad5)") (class "Default")
      (node (ref "D_BUS") (pin "5") (pinfunction "5_5") (pintype "passive"))
    )
    (net (code "269") (name "unconnected-(D_BUS-Pad6)") (class "Default")
      (node (ref "D_BUS") (pin "6") (pinfunction "6_6") (pintype "passive"))
    )
    (net (code "270") (name "unconnected-(D_BUS-Pad7)") (class "Default")
      (node (ref "D_BUS") (pin "7") (pinfunction "7_7") (pintype "passive"))
    )
    (net (code "271") (name "unconnected-(D_BUS-Pad8)") (class "Default")
      (node (ref "D_BUS") (pin "8") (pinfunction "8_8") (pintype "passive"))
    )
    (net (code "272") (name "unconnected-(D_BUS-Pad9)") (class "Default")
      (node (ref "D_BUS") (pin "9") (pinfunction "9_9") (pintype "passive"))
    )
    (net (code "273") (name "unconnected-(D_BUS-Pad10)") (class "Default")
      (node (ref "D_BUS") (pin "10") (pinfunction "10_10") (pintype "passive"))
    )
    (net (code "274") (name "unconnected-(D_BUS-Pad11)") (class "Default")
      (node (ref "D_BUS") (pin "11") (pinfunction "11_11") (pintype "passive"))
    )
    (net (code "275") (name "unconnected-(D_BUS-Pad12)") (class "Default")
      (node (ref "D_BUS") (pin "12") (pinfunction "12_12") (pintype "passive"))
    )
    (net (code "276") (name "unconnected-(D_BUS-Pad13)") (class "Default")
      (node (ref "D_BUS") (pin "13") (pinfunction "13_13") (pintype "passive"))
    )
    (net (code "277") (name "unconnected-(D_BUS-Pad14)") (class "Default")
      (node (ref "D_BUS") (pin "14") (pinfunction "14_14") (pintype "passive"))
    )
    (net (code "278") (name "unconnected-(D_BUS-Pad15)") (class "Default")
      (node (ref "D_BUS") (pin "15") (pinfunction "15_15") (pintype "passive"))
    )
    (net (code "279") (name "unconnected-(D_BUS-Pad16)") (class "Default")
      (node (ref "D_BUS") (pin "16") (pinfunction "16_16") (pintype "passive"))
    )
    (net (code "280") (name "unconnected-(D_BUS-Pad17)") (class "Default")
      (node (ref "D_BUS") (pin "17") (pinfunction "17_17") (pintype "passive"))
    )
    (net (code "281") (name "unconnected-(D_BUS-Pad18)") (class "Default")
      (node (ref "D_BUS") (pin "18") (pinfunction "18_18") (pintype "passive"))
    )
    (net (code "282") (name "unconnected-(D_BUS-Pad19)") (class "Default")
      (node (ref "D_BUS") (pin "19") (pinfunction "19_19") (pintype "passive"))
    )
    (net (code "283") (name "unconnected-(D_BUS-Pad20)") (class "Default")
      (node (ref "D_BUS") (pin "20") (pinfunction "20_20") (pintype "passive"))
    )
    (net (code "284") (name "unconnected-(D_BUS-Pad21)") (class "Default")
      (node (ref "D_BUS") (pin "21") (pinfunction "21_21") (pintype "passive"))
    )
    (net (code "285") (name "unconnected-(D_BUS-Pad22)") (class "Default")
      (node (ref "D_BUS") (pin "22") (pinfunction "22_22") (pintype "passive"))
    )
    (net (code "286") (name "unconnected-(D_BUS-Pad23)") (class "Default")
      (node (ref "D_BUS") (pin "23") (pinfunction "23_23") (pintype "passive"))
    )
    (net (code "287") (name "unconnected-(D_BUS-Pad24)") (class "Default")
      (node (ref "D_BUS") (pin "24") (pinfunction "24_24") (pintype "passive"))
    )
    (net (code "288") (name "unconnected-(D_BUS-Pad25)") (class "Default")
      (node (ref "D_BUS") (pin "25") (pinfunction "25_25") (pintype "passive"))
    )
    (net (code "289") (name "unconnected-(D_BUS-Pad26)") (class "Default")
      (node (ref "D_BUS") (pin "26") (pinfunction "26_26") (pintype "passive"))
    )
    (net (code "290") (name "unconnected-(D_BUS-Pad27)") (class "Default")
      (node (ref "D_BUS") (pin "27") (pinfunction "27_27") (pintype "passive"))
    )
    (net (code "291") (name "unconnected-(D_BUS-Pad28)") (class "Default")
      (node (ref "D_BUS") (pin "28") (pinfunction "28_28") (pintype "passive"))
    )
    (net (code "292") (name "unconnected-(D_BUS-Pad29)") (class "Default")
      (node (ref "D_BUS") (pin "29") (pinfunction "29_29") (pintype "passive"))
    )
    (net (code "293") (name "unconnected-(D_BUS-Pad30)") (class "Default")
      (node (ref "D_BUS") (pin "30") (pinfunction "30_30") (pintype "passive"))
    )
    (net (code "294") (name "unconnected-(D_BUS-Pad31)") (class "Default")
      (node (ref "D_BUS") (pin "31") (pinfunction "31_31") (pintype "passive"))
    )
    (net (code "295") (name "unconnected-(D_BUS-Pad32)") (class "Default")
      (node (ref "D_BUS") (pin "32") (pinfunction "32_32") (pintype "passive"))
    )
    (net (code "296") (name "unconnected-(D_BUS-Pad33)") (class "Default")
      (node (ref "D_BUS") (pin "33") (pinfunction "33_33") (pintype "passive"))
    )
    (net (code "297") (name "unconnected-(D_BUS-Pad34)") (class "Default")
      (node (ref "D_BUS") (pin "34") (pinfunction "34_34") (pintype "passive"))
    )
    (net (code "298") (name "unconnected-(D_BUS-Pad35)") (class "Default")
      (node (ref "D_BUS") (pin "35") (pinfunction "35_35") (pintype "passive"))
    )
    (net (code "299") (name "unconnected-(D_BUS-Pad36)") (class "Default")
      (node (ref "D_BUS") (pin "36") (pinfunction "36_36") (pintype "passive"))
    )
    (net (code "300") (name "unconnected-(D_BUS-Pad37)") (class "Default")
      (node (ref "D_BUS") (pin "37") (pinfunction "37_37") (pintype "passive"))
    )
    (net (code "301") (name "unconnected-(D_BUS-Pad38)") (class "Default")
      (node (ref "D_BUS") (pin "38") (pinfunction "38_38") (pintype "passive"))
    )
    (net (code "302") (name "unconnected-(D_BUS-Pad39)") (class "Default")
      (node (ref "D_BUS") (pin "39") (pinfunction "39_39") (pintype "passive"))
    )
    (net (code "303") (name "unconnected-(D_BUS-Pad40)") (class "Default")
      (node (ref "D_BUS") (pin "40") (pinfunction "40_40") (pintype "passive"))
    )
  )
)
